# Current_SenseSchematic.net
KiCad netlist of a schematic drawn in Altium Designer
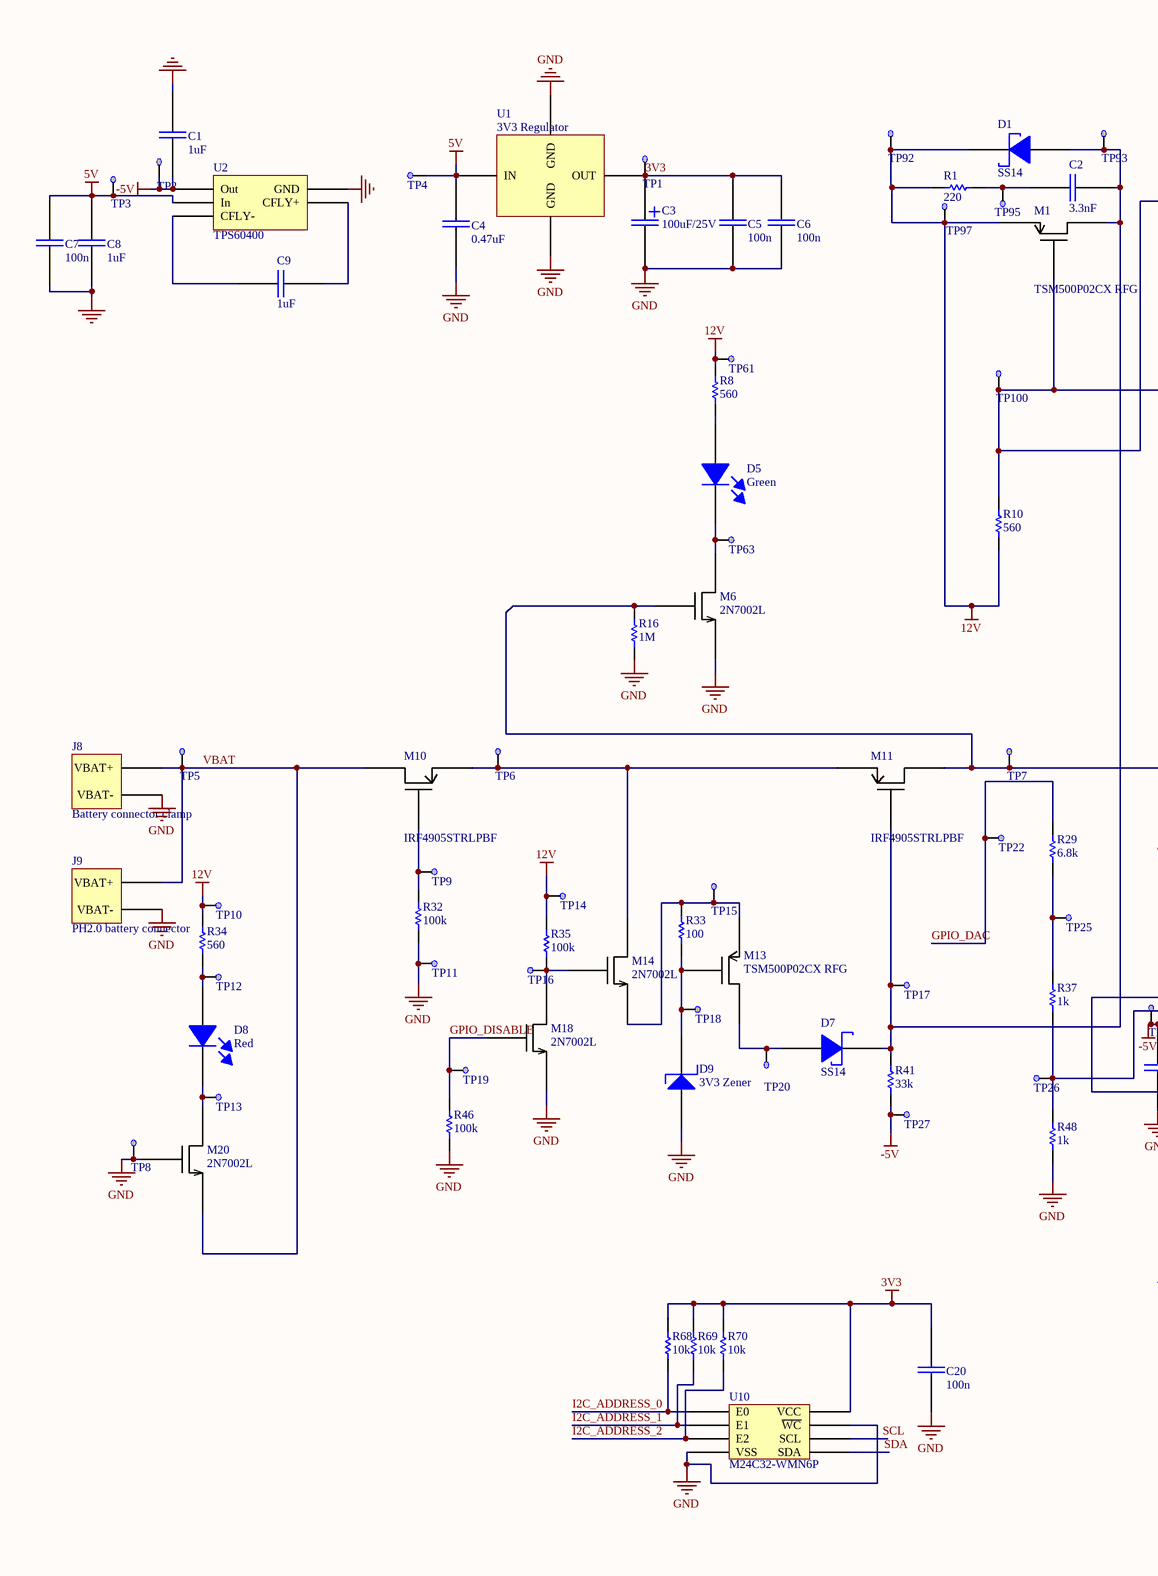
[diagram p0: Current_SenseSchematic.SchDoc, left]
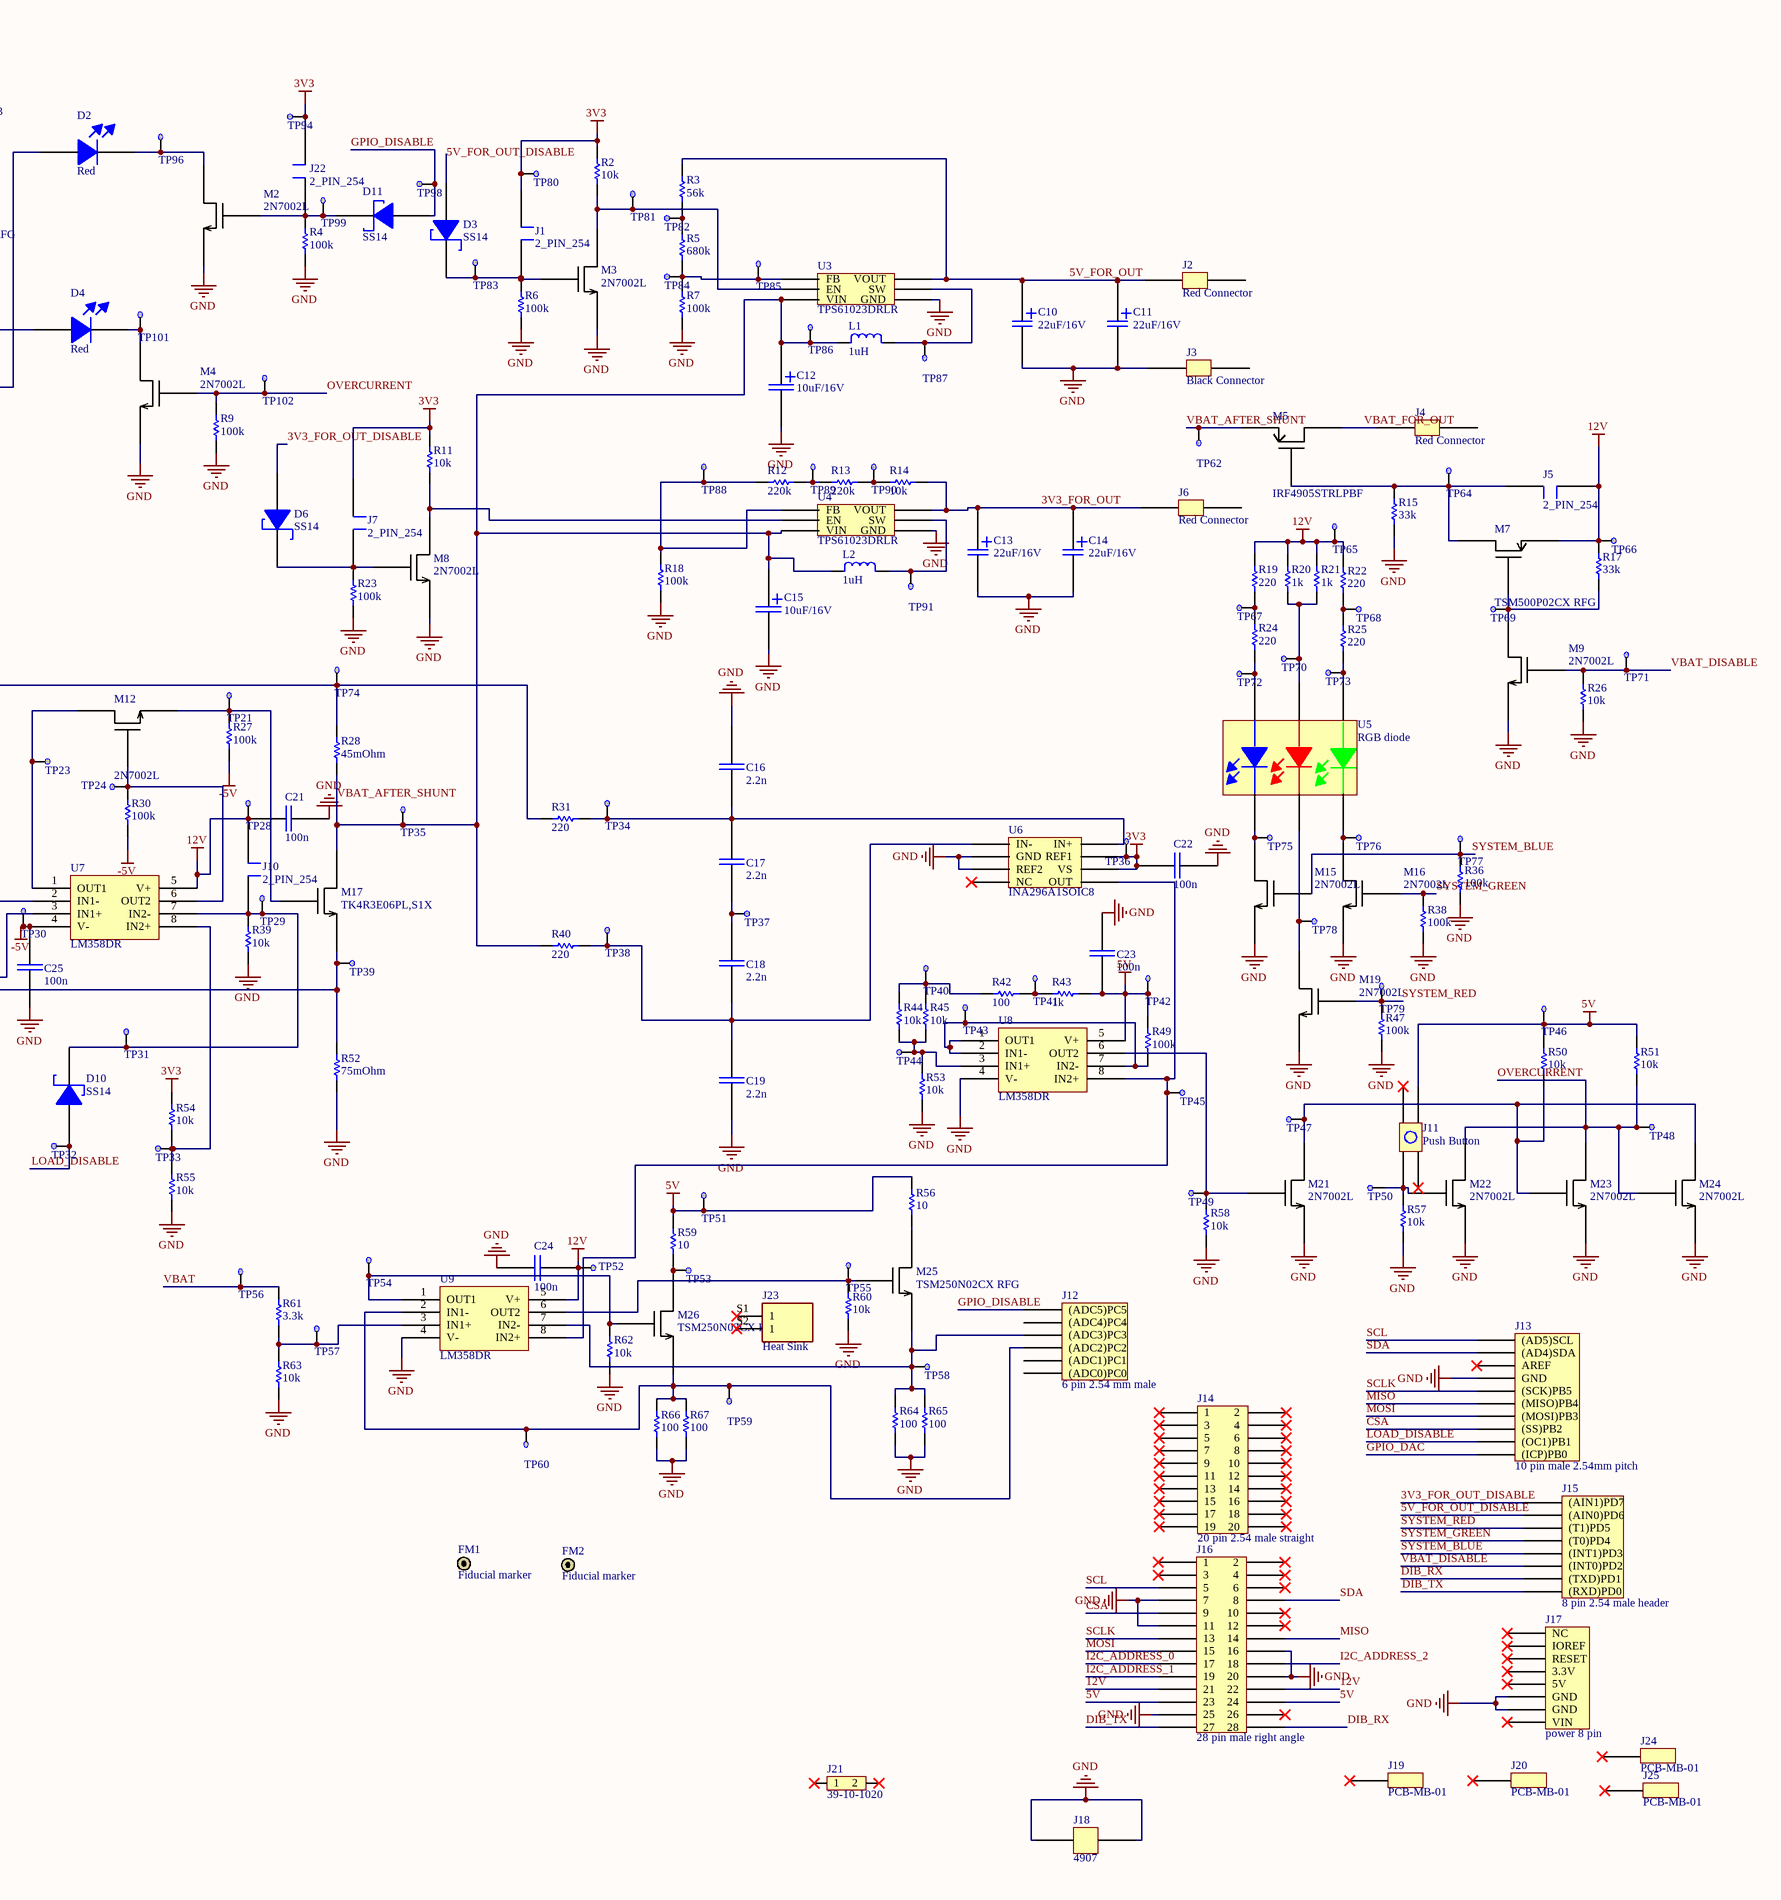
[diagram p1: Current_SenseSchematic.SchDoc, right]

(export (version "E")
  (design (tool "Eeschema 10.0.6"))
  (components
    (comp (ref "C1")
      (value "1uF")
      (footprint "1206Capacitor")
      (description "Multilayer Ceramic Capacitor, 1 uF, 50 V, ± 10%, X7R, 1206 [3216 Metric]")
      (fields
        (field (name "MANUFACTURER") "KEMET")
        (field (name "MANUFACTURER PART NUMBER") "C1206C105K5RACTU")
      )
      (libsource (lib "Current_SenseSchematic") (part "C1206C105K5RACTU"))
    )
    (comp (ref "C2")
      (value "3.3nF")
      (footprint "1206Capacitor")
      (description "Cap Ceramic 0.0033uF 100V C0G 1% SMD 1206 125°C Embossed T/R")
      (fields
        (field (name "MANUFACTURER") "Kyocera AVX")
        (field (name "MANUFACTURER PART NUMBER") "12061A332FAT2A")
      )
      (libsource (lib "Current_SenseSchematic") (part "12061A332FAT2A"))
    )
    (comp (ref "C3")
      (value "100uF/25V")
      (footprint "CAPAE7366X60N")
      (description "Cap, 100Uf, 25V, Alu Elec, Hybrid, Smd Rohs Compliant: Yes ¦Wurth Elektronik 875585344001")
      (fields
        (field (name "MANUFACTURER") "Wurth Electronics")
        (field (name "MANUFACTURER PART NUMBER") "875585344001")
      )
      (libsource (lib "Current_SenseSchematic") (part "875585344001"))
    )
    (comp (ref "C4")
      (value "0.47uF")
      (footprint "1206Capacitor")
      (description "Cap Ceramic 0.47uF 25V X7R 5% SMD 1206 125°C Embossed T/R")
      (fields
        (field (name "MANUFACTURER") "Kyocera AVX")
        (field (name "MANUFACTURER PART NUMBER") "12063C474JAT2A")
      )
      (libsource (lib "Current_SenseSchematic") (part "12063C474JAT2A"))
    )
    (comp (ref "C5")
      (value "100n")
      (footprint "1206Capacitor")
      (description "1206 Standard 100nF Ceramic Multilayer Cap; 50VDC; +150C; X8R Dielectric; +/-10% SMD")
      (fields
        (field (name "MANUFACTURER") "Kyocera AVX")
        (field (name "MANUFACTURER PART NUMBER") "12065F104K4T2A")
      )
      (libsource (lib "Current_SenseSchematic") (part "12065F104K4T2A"))
    )
    (comp (ref "C6")
      (value "100n")
      (footprint "1206Capacitor")
      (description "1206 Standard 100nF Ceramic Multilayer Cap; 50VDC; +150C; X8R Dielectric; +/-10% SMD")
      (fields
        (field (name "MANUFACTURER") "Kyocera AVX")
        (field (name "MANUFACTURER PART NUMBER") "12065F104K4T2A")
      )
      (libsource (lib "Current_SenseSchematic") (part "12065F104K4T2A"))
    )
    (comp (ref "C7")
      (value "100n")
      (footprint "1206Capacitor")
      (description "1206 Standard 100nF Ceramic Multilayer Cap; 50VDC; +150C; X8R Dielectric; +/-10% SMD")
      (fields
        (field (name "MANUFACTURER") "Kyocera AVX")
        (field (name "MANUFACTURER PART NUMBER") "12065F104K4T2A")
      )
      (libsource (lib "Current_SenseSchematic") (part "12065F104K4T2A"))
    )
    (comp (ref "C8")
      (value "1uF")
      (footprint "1206Capacitor")
      (description "Multilayer Ceramic Capacitor, 1 uF, 50 V, ± 10%, X7R, 1206 [3216 Metric]")
      (fields
        (field (name "MANUFACTURER") "KEMET")
        (field (name "MANUFACTURER PART NUMBER") "C1206C105K5RACTU")
      )
      (libsource (lib "Current_SenseSchematic") (part "C1206C105K5RACTU"))
    )
    (comp (ref "C9")
      (value "1uF")
      (footprint "1206Capacitor")
      (description "Multilayer Ceramic Capacitor, 1 uF, 50 V, ± 10%, X7R, 1206 [3216 Metric]")
      (fields
        (field (name "MANUFACTURER") "KEMET")
        (field (name "MANUFACTURER PART NUMBER") "C1206C105K5RACTU")
      )
      (libsource (lib "Current_SenseSchematic") (part "C1206C105K5RACTU"))
    )
    (comp (ref "C10")
      (value "22uF/16V")
      (footprint "22uF/16V")
      (description "Aluminum Electrolytic Capacitors - SMD 22uF 16V")
      (fields
        (field (name "MANUFACTURER") "United Chemi-Con")
        (field (name "MANUFACTURER PART NUMBER") "MVJ16VC22RME60TP")
      )
      (libsource (lib "Current_SenseSchematic") (part "MVJ16VC22RME60TP"))
    )
    (comp (ref "C11")
      (value "22uF/16V")
      (footprint "22uF/16V")
      (description "Aluminum Electrolytic Capacitors - SMD 22uF 16V")
      (fields
        (field (name "MANUFACTURER") "United Chemi-Con")
        (field (name "MANUFACTURER PART NUMBER") "MVJ16VC22RME60TP")
      )
      (libsource (lib "Current_SenseSchematic") (part "MVJ16VC22RME60TP"))
    )
    (comp (ref "C12")
      (value "10uF/16V")
      (footprint "10uF/16V Electrolytic")
      (description "Aluminum Electrolytic Capacitor, 10 uF, 16 V, ± 20%, 1000 hours @ 105°C, Radial Can - SMD")
      (fields
        (field (name "MANUFACTURER") "Panasonic")
        (field (name "MANUFACTURER PART NUMBER") "EEE-HA1C100R")
      )
      (libsource (lib "Current_SenseSchematic") (part "EEE-HA1C100R"))
    )
    (comp (ref "C13")
      (value "22uF/16V")
      (footprint "22uF/16V")
      (description "Aluminum Electrolytic Capacitors - SMD 22uF 16V")
      (fields
        (field (name "MANUFACTURER") "United Chemi-Con")
        (field (name "MANUFACTURER PART NUMBER") "MVJ16VC22RME60TP")
      )
      (libsource (lib "Current_SenseSchematic") (part "MVJ16VC22RME60TP"))
    )
    (comp (ref "C14")
      (value "22uF/16V")
      (footprint "22uF/16V")
      (description "Aluminum Electrolytic Capacitors - SMD 22uF 16V")
      (fields
        (field (name "MANUFACTURER") "United Chemi-Con")
        (field (name "MANUFACTURER PART NUMBER") "MVJ16VC22RME60TP")
      )
      (libsource (lib "Current_SenseSchematic") (part "MVJ16VC22RME60TP"))
    )
    (comp (ref "C15")
      (value "10uF/16V")
      (footprint "10uF/16V Electrolytic")
      (description "Aluminum Electrolytic Capacitor, 10 uF, 16 V, ± 20%, 1000 hours @ 105°C, Radial Can - SMD")
      (fields
        (field (name "MANUFACTURER") "Panasonic")
        (field (name "MANUFACTURER PART NUMBER") "EEE-HA1C100R")
      )
      (libsource (lib "Current_SenseSchematic") (part "EEE-HA1C100R"))
    )
    (comp (ref "C16")
      (value "2.2n")
      (footprint "1206Capacitor")
      (description "1206 2.2 nF 50V ±10 % Tolerance X7R Surface Mount Multilayer Ceramic Capacitor")
      (fields
        (field (name "MANUFACTURER") "Kyocera AVX")
        (field (name "MANUFACTURER PART NUMBER") "12065C222KAZ2A")
      )
      (libsource (lib "Current_SenseSchematic") (part "12065C222KAZ2A"))
    )
    (comp (ref "C17")
      (value "2.2n")
      (footprint "1206Capacitor")
      (description "1206 2.2 nF 50V ±10 % Tolerance X7R Surface Mount Multilayer Ceramic Capacitor")
      (fields
        (field (name "MANUFACTURER") "Kyocera AVX")
        (field (name "MANUFACTURER PART NUMBER") "12065C222KAZ2A")
      )
      (libsource (lib "Current_SenseSchematic") (part "12065C222KAZ2A"))
    )
    (comp (ref "C18")
      (value "2.2n")
      (footprint "1206Capacitor")
      (description "1206 2.2 nF 50V ±10 % Tolerance X7R Surface Mount Multilayer Ceramic Capacitor")
      (fields
        (field (name "MANUFACTURER") "Kyocera AVX")
        (field (name "MANUFACTURER PART NUMBER") "12065C222KAZ2A")
      )
      (libsource (lib "Current_SenseSchematic") (part "12065C222KAZ2A"))
    )
    (comp (ref "C19")
      (value "2.2n")
      (footprint "1206Capacitor")
      (description "1206 2.2 nF 50V ±10 % Tolerance X7R Surface Mount Multilayer Ceramic Capacitor")
      (fields
        (field (name "MANUFACTURER") "Kyocera AVX")
        (field (name "MANUFACTURER PART NUMBER") "12065C222KAZ2A")
      )
      (libsource (lib "Current_SenseSchematic") (part "12065C222KAZ2A"))
    )
    (comp (ref "C20")
      (value "100n")
      (footprint "1206Capacitor")
      (description "1206 Standard 100nF Ceramic Multilayer Cap; 50VDC; +150C; X8R Dielectric; +/-10% SMD")
      (fields
        (field (name "MANUFACTURER") "Kyocera AVX")
        (field (name "MANUFACTURER PART NUMBER") "12065F104K4T2A")
      )
      (libsource (lib "Current_SenseSchematic") (part "12065F104K4T2A"))
    )
    (comp (ref "C21")
      (value "100n")
      (footprint "1206Capacitor")
      (description "1206 Standard 100nF Ceramic Multilayer Cap; 50VDC; +150C; X8R Dielectric; +/-10% SMD")
      (fields
        (field (name "MANUFACTURER") "Kyocera AVX")
        (field (name "MANUFACTURER PART NUMBER") "12065F104K4T2A")
      )
      (libsource (lib "Current_SenseSchematic") (part "12065F104K4T2A"))
    )
    (comp (ref "C22")
      (value "100n")
      (footprint "1206Capacitor")
      (description "1206 Standard 100nF Ceramic Multilayer Cap; 50VDC; +150C; X8R Dielectric; +/-10% SMD")
      (fields
        (field (name "MANUFACTURER") "Kyocera AVX")
        (field (name "MANUFACTURER PART NUMBER") "12065F104K4T2A")
      )
      (libsource (lib "Current_SenseSchematic") (part "12065F104K4T2A"))
    )
    (comp (ref "C23")
      (value "100n")
      (footprint "1206Capacitor")
      (description "1206 Standard 100nF Ceramic Multilayer Cap; 50VDC; +150C; X8R Dielectric; +/-10% SMD")
      (fields
        (field (name "MANUFACTURER") "Kyocera AVX")
        (field (name "MANUFACTURER PART NUMBER") "12065F104K4T2A")
      )
      (libsource (lib "Current_SenseSchematic") (part "12065F104K4T2A"))
    )
    (comp (ref "C24")
      (value "100n")
      (footprint "1206Capacitor")
      (description "1206 Standard 100nF Ceramic Multilayer Cap; 50VDC; +150C; X8R Dielectric; +/-10% SMD")
      (fields
        (field (name "MANUFACTURER") "Kyocera AVX")
        (field (name "MANUFACTURER PART NUMBER") "12065F104K4T2A")
      )
      (libsource (lib "Current_SenseSchematic") (part "12065F104K4T2A"))
    )
    (comp (ref "C25")
      (value "100n")
      (footprint "1206Capacitor")
      (description "1206 Standard 100nF Ceramic Multilayer Cap; 50VDC; +150C; X8R Dielectric; +/-10% SMD")
      (fields
        (field (name "MANUFACTURER") "Kyocera AVX")
        (field (name "MANUFACTURER PART NUMBER") "12065F104K4T2A")
      )
      (libsource (lib "Current_SenseSchematic") (part "12065F104K4T2A"))
    )
    (comp (ref "D1")
      (value "SS14")
      (footprint "DIOM5026X23N")
      (description "SS14 Series 500 mV 1 A 40 V Max Reverse Voltage Schottky Rectifier - DO-214AC")
      (fields (field (name "MANUFACTURER") "ON Semiconductor / Fairchild") (field (name "VOLTAGE") "40V"))
      (libsource (lib "Current_SenseSchematic") (part "SS14"))
    )
    (comp (ref "D2")
      (value "Red")
      (footprint "RED")
      (description "LED Red 20 mcd (Typ.) @ 25 C (Axial) 2.1 V (Typ.) @ 25 C (Forward) PCB")
      (fields
        (field (name "MANUFACTURER") "Lumex")
        (field (name "MANUFACTURER PART NUMBER") "SML-LXL1206GC-TR")
      )
      (libsource (lib "Current_SenseSchematic") (part "SML-LXL1206GC-TR"))
    )
    (comp (ref "D3")
      (value "SS14")
      (footprint "DIOM5026X23N")
      (description "SS14 Series 500 mV 1 A 40 V Max Reverse Voltage Schottky Rectifier - DO-214AC")
      (fields (field (name "MANUFACTURER") "ON Semiconductor / Fairchild") (field (name "VOLTAGE") "40V"))
      (libsource (lib "Current_SenseSchematic") (part "SS14"))
    )
    (comp (ref "D4")
      (value "Red")
      (footprint "RED")
      (description "LED Red 20 mcd (Typ.) @ 25 C (Axial) 2.1 V (Typ.) @ 25 C (Forward) PCB")
      (fields
        (field (name "MANUFACTURER") "Lumex")
        (field (name "MANUFACTURER PART NUMBER") "SML-LXL1206GC-TR")
      )
      (libsource (lib "Current_SenseSchematic") (part "SML-LXL1206GC-TR"))
    )
    (comp (ref "D5")
      (value "Green")
      (footprint "Green")
      (description "Led, Quasarbrite, Green, T-3/4 (1.8Mm), 574 Nm, 2.2 V, 20 Ma, 170 Mcd Rohs Compliant: Yes")
      (fields
        (field (name "MANUFACTURER") "Lumex")
        (field (name "MANUFACTURER PART NUMBER") "SML-LXL1209SUGC-TR")
      )
      (libsource (lib "Current_SenseSchematic") (part "SML-LXL1209SUGC-TR"))
    )
    (comp (ref "D6")
      (value "SS14")
      (footprint "DIOM5026X23N")
      (description "SS14 Series 500 mV 1 A 40 V Max Reverse Voltage Schottky Rectifier - DO-214AC")
      (fields (field (name "MANUFACTURER") "ON Semiconductor / Fairchild") (field (name "VOLTAGE") "40V"))
      (libsource (lib "Current_SenseSchematic") (part "SS14"))
    )
    (comp (ref "D7")
      (value "SS14")
      (footprint "DIOM5026X23N")
      (description "SS14 Series 500 mV 1 A 40 V Max Reverse Voltage Schottky Rectifier - DO-214AC")
      (fields (field (name "MANUFACTURER") "ON Semiconductor / Fairchild") (field (name "VOLTAGE") "40V"))
      (libsource (lib "Current_SenseSchematic") (part "SS14"))
    )
    (comp (ref "D8")
      (value "Red")
      (footprint "RED")
      (description "LED Red 20 mcd (Typ.) @ 25 C (Axial) 2.1 V (Typ.) @ 25 C (Forward) PCB")
      (fields
        (field (name "MANUFACTURER") "Lumex")
        (field (name "MANUFACTURER PART NUMBER") "SML-LXL1206GC-TR")
      )
      (libsource (lib "Current_SenseSchematic") (part "SML-LXL1206GC-TR"))
    )
    (comp (ref "D9")
      (value "3V3 Zener")
      (footprint "DIOMELF3515N")
      (description "MMELF, 500mW, 2%, Small Signal Zener Diode")
      (fields
        (field (name "MANUFACTURER") "Taiwan Semiconductor")
        (field (name "MANUFACTURER PART NUMBER") "BZT55B3V3 L1G")
      )
      (libsource (lib "Current_SenseSchematic") (part "BZT55B3V3 L1G"))
    )
    (comp (ref "D10")
      (value "SS14")
      (footprint "DIOM5026X23N")
      (description "SS14 Series 500 mV 1 A 40 V Max Reverse Voltage Schottky Rectifier - DO-214AC")
      (fields (field (name "MANUFACTURER") "ON Semiconductor / Fairchild") (field (name "VOLTAGE") "40V"))
      (libsource (lib "Current_SenseSchematic") (part "SS14"))
    )
    (comp (ref "D11")
      (value "SS14")
      (footprint "DIOM5026X23N")
      (description "SS14 Series 500 mV 1 A 40 V Max Reverse Voltage Schottky Rectifier - DO-214AC")
      (fields (field (name "MANUFACTURER") "ON Semiconductor / Fairchild") (field (name "VOLTAGE") "40V"))
      (libsource (lib "Current_SenseSchematic") (part "SS14"))
    )
    (comp (ref "FM1")
      (value "Fiducial marker")
      (footprint "Fiducal Marker")
      (libsource (lib "Current_SenseSchematic") (part "FM"))
    )
    (comp (ref "FM2")
      (value "Fiducial marker")
      (footprint "Fiducal Marker")
      (libsource (lib "Current_SenseSchematic") (part "FM"))
    )
    (comp (ref "J1")
      (value "2_PIN_254")
      (footprint "2_PIN_2.54mm")
      (description "Conn Unshrouded Header PL 2 POS 2.54mm Solder ST Thru-Hole")
      (fields (field (name "MANUFACTURER") "Omron") (field (name "MANUFACTURER PART NUMBER") "XG8T-0241"))
      (libsource (lib "Current_SenseSchematic") (part "XG8T-0241"))
    )
    (comp (ref "J2")
      (value "Red Connector")
      (footprint "RED CONNECTOR")
      (description "Connector, Pcb, 2CONTACTS")
      (fields (field (name "MANUFACTURER") "Deltron") (field (name "MANUFACTURER PART NUMBER") "571-0500"))
      (libsource (lib "Current_SenseSchematic") (part "571-0500"))
    )
    (comp (ref "J3")
      (value "Black Connector")
      (footprint "BLACK CONNECTOR")
      (description "Connector, Pcb, 2CONTACTS")
      (fields (field (name "MANUFACTURER") "Deltron") (field (name "MANUFACTURER PART NUMBER") "571-0100"))
      (libsource (lib "Current_SenseSchematic") (part "571-0100"))
    )
    (comp (ref "J4")
      (value "Red Connector")
      (footprint "RED CONNECTOR")
      (description "Connector, Pcb, 2CONTACTS")
      (fields (field (name "MANUFACTURER") "Deltron") (field (name "MANUFACTURER PART NUMBER") "571-0500"))
      (libsource (lib "Current_SenseSchematic") (part "571-0500"))
    )
    (comp (ref "J5")
      (value "2_PIN_254")
      (footprint "2_PIN_2.54mm")
      (description "Conn Unshrouded Header PL 2 POS 2.54mm Solder ST Thru-Hole")
      (fields (field (name "MANUFACTURER") "Omron") (field (name "MANUFACTURER PART NUMBER") "XG8T-0241"))
      (libsource (lib "Current_SenseSchematic") (part "XG8T-0241"))
    )
    (comp (ref "J6")
      (value "Red Connector")
      (footprint "RED CONNECTOR")
      (description "Connector, Pcb, 2CONTACTS")
      (fields (field (name "MANUFACTURER") "Deltron") (field (name "MANUFACTURER PART NUMBER") "571-0500"))
      (libsource (lib "Current_SenseSchematic") (part "571-0500"))
    )
    (comp (ref "J7")
      (value "2_PIN_254")
      (footprint "2_PIN_2.54mm")
      (description "Conn Unshrouded Header PL 2 POS 2.54mm Solder ST Thru-Hole")
      (fields (field (name "MANUFACTURER") "Omron") (field (name "MANUFACTURER PART NUMBER") "XG8T-0241"))
      (libsource (lib "Current_SenseSchematic") (part "XG8T-0241"))
    )
    (comp (ref "J8")
      (value "Battery connector clamp")
      (footprint "2.54mm CLAMP connector")
      (description "Conn PC Board Terminal Block Receptacle 2 POS 2.54mm RA Through Hole 10A")
      (fields
        (field (name "MANUFACTURER") "TE Connectivity")
        (field (name "MANUFACTURER PART NUMBER") "282834-2")
      )
      (libsource (lib "Current_SenseSchematic") (part "282834-2"))
    )
    (comp (ref "J9")
      (value "PH2.0 battery connector")
      (footprint "PH2.0 connector")
      (description "Connector, Header, 2Pos, 1Rows, 2Mm Rohs Compliant: Yes")
      (fields
        (field (name "MANUFACTURER") "TE Connectivity")
        (field (name "MANUFACTURER PART NUMBER") "292133-2")
      )
      (libsource (lib "Current_SenseSchematic") (part "292133-2"))
    )
    (comp (ref "J10")
      (value "2_PIN_254")
      (footprint "2_PIN_2.54mm")
      (description "Conn Unshrouded Header PL 2 POS 2.54mm Solder ST Thru-Hole")
      (fields (field (name "MANUFACTURER") "Omron") (field (name "MANUFACTURER PART NUMBER") "XG8T-0241"))
      (libsource (lib "Current_SenseSchematic") (part "XG8T-0241"))
    )
    (comp (ref "J11")
      (value "Push Button")
      (footprint "PUSH_BUTTON")
      (description "Switch Tactile N.O. SPST Round Button Gull Wing 0.05A 12VDC 1.57N SMD Tube")
      (fields
        (field (name "MANUFACTURER") "Diptronics")
        (field (name "MANUFACTURER PART NUMBER") "DTSM-61N-V-B")
      )
      (libsource (lib "Current_SenseSchematic") (part "DTSM-61N-V-B"))
    )
    (comp (ref "J12")
      (value "6 pin 2.54 mm male")
      (footprint "6_pin_header_male_2_54")
      (description "2.54mm (0.1\") Pitch SIL Vertical PC Tail Pin Header, 7mm mating pin height, tin, 6 contacts")
      (fields (field (name "MANUFACTURER") "Harwin") (field (name "MANUFACTURER PART NUMBER") "M20-9730646"))
      (libsource (lib "Current_SenseSchematic") (part "M20-9730646"))
    )
    (comp (ref "J13")
      (value "10 pin male 2.54mm pitch")
      (footprint "10_pin_header_male_2_54")
      (description "Conn Unshrouded Header HDR 50 POS 2.54mm Solder ST Thru-Hole Box")
      (fields
        (field (name "MANUFACTURER") "TE Connectivity")
        (field (name "MANUFACTURER PART NUMBER") "5-825433-0")
      )
      (libsource (lib "Current_SenseSchematic") (part "5-825433-0"))
    )
    (comp (ref "J14")
      (value "20 pin 2.54 male straight")
      (footprint "20_pin_header_angled_female_2_54_mm")
      (description "Conn, Header, 20POS, 2ROW, 2.54MM Rohs Compliant: Yes")
      (fields (field (name "MANUFACTURER") "Harwin") (field (name "MANUFACTURER PART NUMBER") "M20-9721045"))
      (libsource (lib "Current_SenseSchematic") (part "M20-9721045"))
    )
    (comp (ref "J15")
      (value "8 pin 2.54 male header")
      (footprint "8_pin_header_male_2_54")
      (description "2.54MM Pitch, Srsw, T/h, H")
      (fields (field (name "MANUFACTURER") "Molex") (field (name "MANUFACTURER PART NUMBER") "0878910808"))
      (libsource (lib "Current_SenseSchematic") (part "0878910808"))
    )
    (comp (ref "J16")
      (value "28 pin male right angle")
      (footprint "28_Pin_header_right_angle")
      (description "Headers & Wire Housings 28P 2R BRKAWAY HDR 2.54MM RA L-PRO SN")
      (fields (field (name "MANUFACTURER") "Molex") (field (name "MANUFACTURER PART NUMBER") "0717640028"))
      (libsource (lib "Current_SenseSchematic") (part "0717640028"))
    )
    (comp (ref "J17")
      (value "power 8 pin")
      (footprint "8_pin_header_male_2_54")
      (description "2.54MM Pitch, Srsw, T/h, H")
      (fields (field (name "MANUFACTURER") "Molex") (field (name "MANUFACTURER PART NUMBER") "0878910808"))
      (libsource (lib "Current_SenseSchematic") (part "0878910808_Power"))
    )
    (comp (ref "J18")
      (value "4907")
      (footprint "4907_footprint")
      (description "USB C SMT / THM Jack Connector - Power Only - Pack of 10")
      (fields (field (name "MANUFACTURER") "Keystone Electronics"))
      (libsource (lib "Current_SenseSchematic") (part "4907"))
    )
    (comp (ref "J19")
      (value "PCB-MB-01")
      (footprint "PCB-MB-01")
      (description "Installation BLock Colour: Transparent Material: Nylon 6/6 RMS-01")
      (fields (field (name "MANUFACTURER") "Essentra"))
      (libsource (lib "Current_SenseSchematic") (part "PCB-MB-01"))
    )
    (comp (ref "J20")
      (value "PCB-MB-01")
      (footprint "PCB-MB-01")
      (description "Installation BLock Colour: Transparent Material: Nylon 6/6 RMS-01")
      (fields (field (name "MANUFACTURER") "Essentra"))
      (libsource (lib "Current_SenseSchematic") (part "PCB-MB-01"))
    )
    (comp (ref "J21")
      (value "39-10-1020")
      (footprint "39-30-1020")
      (description "Connector Wire to Board Header 2 Position 4.2mm Solder Right Angle Thru-Hole Bag")
      (fields (field (name "MANUFACTURER") "Molex") (field (name "MANUFACTURER PART NUMBER") "0039301020+"))
      (libsource (lib "Current_SenseSchematic") (part "0039301020+"))
    )
    (comp (ref "J22")
      (value "2_PIN_254")
      (footprint "2_PIN_2.54mm")
      (description "Conn Unshrouded Header PL 2 POS 2.54mm Solder ST Thru-Hole")
      (fields (field (name "MANUFACTURER") "Omron") (field (name "MANUFACTURER PART NUMBER") "XG8T-0241"))
      (libsource (lib "Current_SenseSchematic") (part "XG8T-0241"))
    )
    (comp (ref "J23")
      (value "Heat Sink")
      (footprint "HEAT_SINK")
      (description "Heat Sink Passive TO-220 Radial Thru-Hole Aluminum 5.5°C/W Black Anodized")
      (fields
        (field (name "MANUFACTURER") "Aavid Thermalloy")
        (field (name "MANUFACTURER PART NUMBER") "529702B02500G")
      )
      (libsource (lib "Current_SenseSchematic") (part "529702B02500G"))
    )
    (comp (ref "J24")
      (value "PCB-MB-01")
      (footprint "PCB-MB-01")
      (description "Installation BLock Colour: Transparent Material: Nylon 6/6 RMS-01")
      (fields (field (name "MANUFACTURER") "Essentra"))
      (libsource (lib "Current_SenseSchematic") (part "PCB-MB-01"))
    )
    (comp (ref "J25")
      (value "PCB-MB-01")
      (footprint "PCB-MB-01")
      (description "Installation BLock Colour: Transparent Material: Nylon 6/6 RMS-01")
      (fields (field (name "MANUFACTURER") "Essentra"))
      (libsource (lib "Current_SenseSchematic") (part "PCB-MB-01"))
    )
    (comp (ref "L1")
      (value "1uH")
      (footprint "PA4333_7.4x6.8x3.2mm")
      (description "Drum Core Shielded Power Inductor Wirewound Ferrite 1uH 20% 1MHz 9.5A SMD T/R")
      (fields (field (name "MANUFACTURER") "Pulse") (field (name "MANUFACTURER PART NUMBER") "PA4333.102NLT"))
      (libsource (lib "Current_SenseSchematic") (part "PA4333.102NLT"))
    )
    (comp (ref "L2")
      (value "1uH")
      (footprint "PA4333_7.4x6.8x3.2mm")
      (description "Drum Core Shielded Power Inductor Wirewound Ferrite 1uH 20% 1MHz 9.5A SMD T/R")
      (fields (field (name "MANUFACTURER") "Pulse") (field (name "MANUFACTURER PART NUMBER") "PA4333.102NLT"))
      (libsource (lib "Current_SenseSchematic") (part "PA4333.102NLT"))
    )
    (comp (ref "M1")
      (value "TSM500P02CX RFG")
      (footprint "SOT95P240X100-3N")
      (description "Transistor Mosfet P-ch 20V 4.7A 3-PIN SOT-23 T/r")
      (fields (field (name "MANUFACTURER") "Taiwan Semiconductor"))
      (libsource (lib "Current_SenseSchematic") (part "TSM500P02CX RFG"))
    )
    (comp (ref "M2")
      (value "2N7002L")
      (footprint "SOT95P240X100-3N")
      (description "Mosfet, N-ch, Vdss 60VDC, Rds(on) 7.5 Ohms, ID+/-115MA, SOT-23 (TO-236), Pd 225MW, -55C")
      (fields (field (name "MANUFACTURER") "ON Semiconductor / Fairchild"))
      (libsource (lib "Current_SenseSchematic") (part "2N7002L"))
    )
    (comp (ref "M3")
      (value "2N7002L")
      (footprint "SOT95P240X100-3N")
      (description "Mosfet, N-ch, Vdss 60VDC, Rds(on) 7.5 Ohms, ID+/-115MA, SOT-23 (TO-236), Pd 225MW, -55C")
      (fields (field (name "MANUFACTURER") "ON Semiconductor / Fairchild"))
      (libsource (lib "Current_SenseSchematic") (part "2N7002L"))
    )
    (comp (ref "M4")
      (value "2N7002L")
      (footprint "SOT95P240X100-3N")
      (description "Mosfet, N-ch, Vdss 60VDC, Rds(on) 7.5 Ohms, ID+/-115MA, SOT-23 (TO-236), Pd 225MW, -55C")
      (fields (field (name "MANUFACTURER") "ON Semiconductor / Fairchild"))
      (libsource (lib "Current_SenseSchematic") (part "2N7002L"))
    )
    (comp (ref "M5")
      (value "IRF4905STRLPBF")
      (footprint "DPAK254P1524X483-3L")
      (description "Transistor: P-MOSFET; unipolar; -55V; -74A; 0.02ohm; 3.8W; -55+175 deg.C; SMD; TO263 (D2PAK)")
      (fields (field (name "MANUFACTURER") "Infineon"))
      (libsource (lib "Current_SenseSchematic") (part "IRF4905STRLPBF"))
    )
    (comp (ref "M6")
      (value "2N7002L")
      (footprint "SOT95P240X100-3N")
      (description "Mosfet, N-ch, Vdss 60VDC, Rds(on) 7.5 Ohms, ID+/-115MA, SOT-23 (TO-236), Pd 225MW, -55C")
      (fields (field (name "MANUFACTURER") "ON Semiconductor / Fairchild"))
      (libsource (lib "Current_SenseSchematic") (part "2N7002L"))
    )
    (comp (ref "M7")
      (value "TSM500P02CX RFG")
      (footprint "SOT95P240X100-3N")
      (description "Transistor Mosfet P-ch 20V 4.7A 3-PIN SOT-23 T/r")
      (fields (field (name "MANUFACTURER") "Taiwan Semiconductor"))
      (libsource (lib "Current_SenseSchematic") (part "TSM500P02CX RFG"))
    )
    (comp (ref "M8")
      (value "2N7002L")
      (footprint "SOT95P240X100-3N")
      (description "Mosfet, N-ch, Vdss 60VDC, Rds(on) 7.5 Ohms, ID+/-115MA, SOT-23 (TO-236), Pd 225MW, -55C")
      (fields (field (name "MANUFACTURER") "ON Semiconductor / Fairchild"))
      (libsource (lib "Current_SenseSchematic") (part "2N7002L"))
    )
    (comp (ref "M9")
      (value "2N7002L")
      (footprint "SOT95P240X100-3N")
      (description "Mosfet, N-ch, Vdss 60VDC, Rds(on) 7.5 Ohms, ID+/-115MA, SOT-23 (TO-236), Pd 225MW, -55C")
      (fields (field (name "MANUFACTURER") "ON Semiconductor / Fairchild"))
      (libsource (lib "Current_SenseSchematic") (part "2N7002L"))
    )
    (comp (ref "M10")
      (value "IRF4905STRLPBF")
      (footprint "DPAK254P1524X483-3L")
      (description "Transistor: P-MOSFET; unipolar; -55V; -74A; 0.02ohm; 3.8W; -55+175 deg.C; SMD; TO263 (D2PAK)")
      (fields (field (name "MANUFACTURER") "Infineon"))
      (libsource (lib "Current_SenseSchematic") (part "IRF4905STRLPBF"))
    )
    (comp (ref "M11")
      (value "IRF4905STRLPBF")
      (footprint "DPAK254P1524X483-3L")
      (description "Transistor: P-MOSFET; unipolar; -55V; -74A; 0.02ohm; 3.8W; -55+175 deg.C; SMD; TO263 (D2PAK)")
      (fields (field (name "MANUFACTURER") "Infineon"))
      (libsource (lib "Current_SenseSchematic") (part "IRF4905STRLPBF"))
    )
    (comp (ref "M12")
      (value "2N7002L")
      (footprint "SOT95P240X100-3N")
      (description "Mosfet, N-ch, Vdss 60VDC, Rds(on) 7.5 Ohms, ID+/-115MA, SOT-23 (TO-236), Pd 225MW, -55C")
      (fields (field (name "MANUFACTURER") "ON Semiconductor / Fairchild"))
      (libsource (lib "Current_SenseSchematic") (part "2N7002L"))
    )
    (comp (ref "M13")
      (value "TSM500P02CX RFG")
      (footprint "SOT95P240X100-3N")
      (description "Transistor Mosfet P-ch 20V 4.7A 3-PIN SOT-23 T/r")
      (fields (field (name "MANUFACTURER") "Taiwan Semiconductor"))
      (libsource (lib "Current_SenseSchematic") (part "TSM500P02CX RFG"))
    )
    (comp (ref "M14")
      (value "2N7002L")
      (footprint "SOT95P240X100-3N")
      (description "Mosfet, N-ch, Vdss 60VDC, Rds(on) 7.5 Ohms, ID+/-115MA, SOT-23 (TO-236), Pd 225MW, -55C")
      (fields (field (name "MANUFACTURER") "ON Semiconductor / Fairchild"))
      (libsource (lib "Current_SenseSchematic") (part "2N7002L"))
    )
    (comp (ref "M15")
      (value "2N7002L")
      (footprint "SOT95P240X100-3N")
      (description "Mosfet, N-ch, Vdss 60VDC, Rds(on) 7.5 Ohms, ID+/-115MA, SOT-23 (TO-236), Pd 225MW, -55C")
      (fields (field (name "MANUFACTURER") "ON Semiconductor / Fairchild"))
      (libsource (lib "Current_SenseSchematic") (part "2N7002L"))
    )
    (comp (ref "M16")
      (value "2N7002L")
      (footprint "SOT95P240X100-3N")
      (description "Mosfet, N-ch, Vdss 60VDC, Rds(on) 7.5 Ohms, ID+/-115MA, SOT-23 (TO-236), Pd 225MW, -55C")
      (fields (field (name "MANUFACTURER") "ON Semiconductor / Fairchild"))
      (libsource (lib "Current_SenseSchematic") (part "2N7002L"))
    )
    (comp (ref "M17")
      (value "TK4R3E06PL,S1X")
      (footprint "TO-220-3")
      (description "X35 Pb-F Power Mosfet Transistor To-220 Pd=87W F=1Mhz")
      (fields (field (name "MANUFACTURER") "Toshiba"))
      (libsource (lib "Current_SenseSchematic") (part "TK4R3E06PL,S1X"))
    )
    (comp (ref "M18")
      (value "2N7002L")
      (footprint "SOT95P240X100-3N")
      (description "Mosfet, N-ch, Vdss 60VDC, Rds(on) 7.5 Ohms, ID+/-115MA, SOT-23 (TO-236), Pd 225MW, -55C")
      (fields (field (name "MANUFACTURER") "ON Semiconductor / Fairchild"))
      (libsource (lib "Current_SenseSchematic") (part "2N7002L"))
    )
    (comp (ref "M19")
      (value "2N7002L")
      (footprint "SOT95P240X100-3N")
      (description "Mosfet, N-ch, Vdss 60VDC, Rds(on) 7.5 Ohms, ID+/-115MA, SOT-23 (TO-236), Pd 225MW, -55C")
      (fields (field (name "MANUFACTURER") "ON Semiconductor / Fairchild"))
      (libsource (lib "Current_SenseSchematic") (part "2N7002L"))
    )
    (comp (ref "M20")
      (value "2N7002L")
      (footprint "SOT95P240X100-3N")
      (description "Mosfet, N-ch, Vdss 60VDC, Rds(on) 7.5 Ohms, ID+/-115MA, SOT-23 (TO-236), Pd 225MW, -55C")
      (fields (field (name "MANUFACTURER") "ON Semiconductor / Fairchild"))
      (libsource (lib "Current_SenseSchematic") (part "2N7002L"))
    )
    (comp (ref "M21")
      (value "2N7002L")
      (footprint "SOT95P240X100-3N")
      (description "Mosfet, N-ch, Vdss 60VDC, Rds(on) 7.5 Ohms, ID+/-115MA, SOT-23 (TO-236), Pd 225MW, -55C")
      (fields (field (name "MANUFACTURER") "ON Semiconductor / Fairchild"))
      (libsource (lib "Current_SenseSchematic") (part "2N7002L"))
    )
    (comp (ref "M22")
      (value "2N7002L")
      (footprint "SOT95P240X100-3N")
      (description "Mosfet, N-ch, Vdss 60VDC, Rds(on) 7.5 Ohms, ID+/-115MA, SOT-23 (TO-236), Pd 225MW, -55C")
      (fields (field (name "MANUFACTURER") "ON Semiconductor / Fairchild"))
      (libsource (lib "Current_SenseSchematic") (part "2N7002L"))
    )
    (comp (ref "M23")
      (value "2N7002L")
      (footprint "SOT95P240X100-3N")
      (description "Mosfet, N-ch, Vdss 60VDC, Rds(on) 7.5 Ohms, ID+/-115MA, SOT-23 (TO-236), Pd 225MW, -55C")
      (fields (field (name "MANUFACTURER") "ON Semiconductor / Fairchild"))
      (libsource (lib "Current_SenseSchematic") (part "2N7002L"))
    )
    (comp (ref "M24")
      (value "2N7002L")
      (footprint "SOT95P240X100-3N")
      (description "Mosfet, N-ch, Vdss 60VDC, Rds(on) 7.5 Ohms, ID+/-115MA, SOT-23 (TO-236), Pd 225MW, -55C")
      (fields (field (name "MANUFACTURER") "ON Semiconductor / Fairchild"))
      (libsource (lib "Current_SenseSchematic") (part "2N7002L"))
    )
    (comp (ref "M25")
      (value "TSM250N02CX RFG")
      (footprint "SOT95P240X100-3N")
      (description "Transistor Power MOSFET N-CH 20V 5.8A 3-Pin SOT-23 T/R")
      (fields (field (name "MANUFACTURER") "Taiwan Semiconductor"))
      (libsource (lib "Current_SenseSchematic") (part "TSM250N02CX RFG"))
    )
    (comp (ref "M26")
      (value "TSM250N02CX RFG")
      (footprint "SOT95P240X100-3N")
      (description "Transistor Power MOSFET N-CH 20V 5.8A 3-Pin SOT-23 T/R")
      (fields (field (name "MANUFACTURER") "Taiwan Semiconductor"))
      (libsource (lib "Current_SenseSchematic") (part "TSM250N02CX RFG"))
    )
    (comp (ref "R1")
      (value "220")
      (footprint "RESISTOR1206")
      (description "Res, Aec-Q200, 220R, 1%, 0.5W, 1206 Rohs Compliant: Yes ¦Vishay RCC1206220RFKEA")
      (fields
        (field (name "MANUFACTURER") "Vishay Dale")
        (field (name "MANUFACTURER PART NUMBER") "RCC1206220RFKEA")
      )
      (libsource (lib "Current_SenseSchematic") (part "RCC1206220RFKEA"))
    )
    (comp (ref "R2")
      (value "10k")
      (footprint "RESISTOR1206")
      (description "SMD Chip Resistor, 10 kOhm, ± 5%, 250 mW, 1206 [3216 Metric], Thick Film, General Purpose")
      (fields
        (field (name "MANUFACTURER") "Bourns")
        (field (name "MANUFACTURER PART NUMBER") "CR1206-JW-103ELF")
      )
      (libsource (lib "Current_SenseSchematic") (part "CR1206-JW-103ELF"))
    )
    (comp (ref "R3")
      (value "56k")
      (footprint "RESISTOR1206")
      (description "Res Thick Film 1206 56K Ohm 1% 1/4W ±100ppm/°C Molded SMD SMD Paper Tape on Plastic Reel")
      (fields
        (field (name "MANUFACTURER") "Bourns")
        (field (name "MANUFACTURER PART NUMBER") "CR1206-FX-5602ELF")
      )
      (libsource (lib "Current_SenseSchematic") (part "CR1206-FX-5602ELF"))
    )
    (comp (ref "R4")
      (value "100k")
      (footprint "RESISTOR1206")
      (description "Res Thick Film 1206 100kOhm 1/4W Molded Paper T/R")
      (fields
        (field (name "MANUFACTURER") "Vishay Dale")
        (field (name "MANUFACTURER PART NUMBER") "RCG1206100KJNEA")
      )
      (libsource (lib "Current_SenseSchematic") (part "RCG1206100KJNEA"))
    )
    (comp (ref "R5")
      (value "680k")
      (footprint "RESISTOR1206")
      (description "RES SMD 680K OHM 5% 1/4W 1206")
      (fields
        (field (name "MANUFACTURER") "Bourns")
        (field (name "MANUFACTURER PART NUMBER") "CR1206-JW-684ELF")
      )
      (libsource (lib "Current_SenseSchematic") (part "CR1206-JW-684ELF"))
    )
    (comp (ref "R6")
      (value "100k")
      (footprint "RESISTOR1206")
      (description "Res Thick Film 1206 100kOhm 1/4W Molded Paper T/R")
      (fields
        (field (name "MANUFACTURER") "Vishay Dale")
        (field (name "MANUFACTURER PART NUMBER") "RCG1206100KJNEA")
      )
      (libsource (lib "Current_SenseSchematic") (part "RCG1206100KJNEA"))
    )
    (comp (ref "R7")
      (value "100k")
      (footprint "RESISTOR1206")
      (description "Res Thick Film 1206 100kOhm 1/4W Molded Paper T/R")
      (fields
        (field (name "MANUFACTURER") "Vishay Dale")
        (field (name "MANUFACTURER PART NUMBER") "RCG1206100KJNEA")
      )
      (libsource (lib "Current_SenseSchematic") (part "RCG1206100KJNEA"))
    )
    (comp (ref "R8")
      (value "560")
      (footprint "RESISTOR1206")
      (description "Res Thkflm D25/1206 560R Ohm 1% 100 ET6 E3 SMD")
      (fields
        (field (name "MANUFACTURER") "Vishay Dale")
        (field (name "MANUFACTURER PART NUMBER") "CRCW1206560RFKEC")
      )
      (libsource (lib "Current_SenseSchematic") (part "CRCW1206560RFKEC"))
    )
    (comp (ref "R9")
      (value "100k")
      (footprint "RESISTOR1206")
      (description "Res Thick Film 1206 100kOhm 1/4W Molded Paper T/R")
      (fields
        (field (name "MANUFACTURER") "Vishay Dale")
        (field (name "MANUFACTURER PART NUMBER") "RCG1206100KJNEA")
      )
      (libsource (lib "Current_SenseSchematic") (part "RCG1206100KJNEA"))
    )
    (comp (ref "R10")
      (value "560")
      (footprint "RESISTOR1206")
      (description "Res Thkflm D25/1206 560R Ohm 1% 100 ET6 E3 SMD")
      (fields
        (field (name "MANUFACTURER") "Vishay Dale")
        (field (name "MANUFACTURER PART NUMBER") "CRCW1206560RFKEC")
      )
      (libsource (lib "Current_SenseSchematic") (part "CRCW1206560RFKEC"))
    )
    (comp (ref "R11")
      (value "10k")
      (footprint "RESISTOR1206")
      (description "SMD Chip Resistor, 10 kOhm, ± 5%, 250 mW, 1206 [3216 Metric], Thick Film, General Purpose")
      (fields
        (field (name "MANUFACTURER") "Bourns")
        (field (name "MANUFACTURER PART NUMBER") "CR1206-JW-103ELF")
      )
      (libsource (lib "Current_SenseSchematic") (part "CR1206-JW-103ELF"))
    )
    (comp (ref "R12")
      (value "220k")
      (footprint "RESISTOR1206")
      (description "Resistor Thick Film 220kOhm 5% 2-Pin 1206 T/R")
      (fields
        (field (name "MANUFACTURER") "Bourns")
        (field (name "MANUFACTURER PART NUMBER") "CHP1206AJW-224ELF")
      )
      (libsource (lib "Current_SenseSchematic") (part "CHP1206AJW-224ELF"))
    )
    (comp (ref "R13")
      (value "220k")
      (footprint "RESISTOR1206")
      (description "Resistor Thick Film 220kOhm 5% 2-Pin 1206 T/R")
      (fields
        (field (name "MANUFACTURER") "Bourns")
        (field (name "MANUFACTURER PART NUMBER") "CHP1206AJW-224ELF")
      )
      (libsource (lib "Current_SenseSchematic") (part "CHP1206AJW-224ELF"))
    )
    (comp (ref "R14")
      (value "10k")
      (footprint "RESISTOR1206")
      (description "SMD Chip Resistor, 10 kOhm, ± 5%, 250 mW, 1206 [3216 Metric], Thick Film, General Purpose")
      (fields
        (field (name "MANUFACTURER") "Bourns")
        (field (name "MANUFACTURER PART NUMBER") "CR1206-JW-103ELF")
      )
      (libsource (lib "Current_SenseSchematic") (part "CR1206-JW-103ELF"))
    )
    (comp (ref "R15")
      (value "33k")
      (footprint "RESISTOR1206")
      (description "SMD Chip Resistor, 33 kOhm, ± 5%, 250 mW, 1206 [3216 Metric], Thick Film, General Purpose")
      (fields
        (field (name "MANUFACTURER") "Yageo")
        (field (name "MANUFACTURER PART NUMBER") "RC1206JR-0733KL")
      )
      (libsource (lib "Current_SenseSchematic") (part "RC1206JR-0733KL"))
    )
    (comp (ref "R16")
      (value "1M")
      (footprint "RESISTOR1206")
      (description "SMD Chip Resistor, 1 MOhm, ± 5%, 250 mW, 1206 [3216 Metric], Thick Film, General Purpose")
      (fields
        (field (name "MANUFACTURER") "Bourns")
        (field (name "MANUFACTURER PART NUMBER") "CR1206-JW-105ELF")
      )
      (libsource (lib "Current_SenseSchematic") (part "CR1206-JW-105ELF"))
    )
    (comp (ref "R17")
      (value "33k")
      (footprint "RESISTOR1206")
      (description "SMD Chip Resistor, 33 kOhm, ± 5%, 250 mW, 1206 [3216 Metric], Thick Film, General Purpose")
      (fields
        (field (name "MANUFACTURER") "Yageo")
        (field (name "MANUFACTURER PART NUMBER") "RC1206JR-0733KL")
      )
      (libsource (lib "Current_SenseSchematic") (part "RC1206JR-0733KL"))
    )
    (comp (ref "R18")
      (value "100k")
      (footprint "RESISTOR1206")
      (description "Res Thick Film 1206 100kOhm 1/4W Molded Paper T/R")
      (fields
        (field (name "MANUFACTURER") "Vishay Dale")
        (field (name "MANUFACTURER PART NUMBER") "RCG1206100KJNEA")
      )
      (libsource (lib "Current_SenseSchematic") (part "RCG1206100KJNEA"))
    )
    (comp (ref "R19")
      (value "220")
      (footprint "RESISTOR1206")
      (description "Res, Aec-Q200, 220R, 1%, 0.5W, 1206 Rohs Compliant: Yes ¦Vishay RCC1206220RFKEA")
      (fields
        (field (name "MANUFACTURER") "Vishay Dale")
        (field (name "MANUFACTURER PART NUMBER") "RCC1206220RFKEA")
      )
      (libsource (lib "Current_SenseSchematic") (part "RCC1206220RFKEA"))
    )
    (comp (ref "R20")
      (value "1k")
      (footprint "RESISTOR1206")
      (description "Res Thick Film 1206 1kOhm 5% 1/4W ±200ppm/K Molded Paper Tape")
      (fields
        (field (name "MANUFACTURER") "Vishay Dale")
        (field (name "MANUFACTURER PART NUMBER") "RCA12061K00JNEA")
      )
      (libsource (lib "Current_SenseSchematic") (part "RCA12061K00JNEA"))
    )
    (comp (ref "R21")
      (value "1k")
      (footprint "RESISTOR1206")
      (description "Res Thick Film 1206 1kOhm 5% 1/4W ±200ppm/K Molded Paper Tape")
      (fields
        (field (name "MANUFACTURER") "Vishay Dale")
        (field (name "MANUFACTURER PART NUMBER") "RCA12061K00JNEA")
      )
      (libsource (lib "Current_SenseSchematic") (part "RCA12061K00JNEA"))
    )
    (comp (ref "R22")
      (value "220")
      (footprint "RESISTOR1206")
      (description "Res, Aec-Q200, 220R, 1%, 0.5W, 1206 Rohs Compliant: Yes ¦Vishay RCC1206220RFKEA")
      (fields
        (field (name "MANUFACTURER") "Vishay Dale")
        (field (name "MANUFACTURER PART NUMBER") "RCC1206220RFKEA")
      )
      (libsource (lib "Current_SenseSchematic") (part "RCC1206220RFKEA"))
    )
    (comp (ref "R23")
      (value "100k")
      (footprint "RESISTOR1206")
      (description "Res Thick Film 1206 100kOhm 1/4W Molded Paper T/R")
      (fields
        (field (name "MANUFACTURER") "Vishay Dale")
        (field (name "MANUFACTURER PART NUMBER") "RCG1206100KJNEA")
      )
      (libsource (lib "Current_SenseSchematic") (part "RCG1206100KJNEA"))
    )
    (comp (ref "R24")
      (value "220")
      (footprint "RESISTOR1206")
      (description "Res, Aec-Q200, 220R, 1%, 0.5W, 1206 Rohs Compliant: Yes ¦Vishay RCC1206220RFKEA")
      (fields
        (field (name "MANUFACTURER") "Vishay Dale")
        (field (name "MANUFACTURER PART NUMBER") "RCC1206220RFKEA")
      )
      (libsource (lib "Current_SenseSchematic") (part "RCC1206220RFKEA"))
    )
    (comp (ref "R25")
      (value "220")
      (footprint "RESISTOR1206")
      (description "Res, Aec-Q200, 220R, 1%, 0.5W, 1206 Rohs Compliant: Yes ¦Vishay RCC1206220RFKEA")
      (fields
        (field (name "MANUFACTURER") "Vishay Dale")
        (field (name "MANUFACTURER PART NUMBER") "RCC1206220RFKEA")
      )
      (libsource (lib "Current_SenseSchematic") (part "RCC1206220RFKEA"))
    )
    (comp (ref "R26")
      (value "10k")
      (footprint "RESISTOR1206")
      (description "SMD Chip Resistor, 10 kOhm, ± 5%, 250 mW, 1206 [3216 Metric], Thick Film, General Purpose")
      (fields
        (field (name "MANUFACTURER") "Bourns")
        (field (name "MANUFACTURER PART NUMBER") "CR1206-JW-103ELF")
      )
      (libsource (lib "Current_SenseSchematic") (part "CR1206-JW-103ELF"))
    )
    (comp (ref "R27")
      (value "100k")
      (footprint "RESISTOR1206")
      (description "Res Thick Film 1206 100kOhm 1/4W Molded Paper T/R")
      (fields
        (field (name "MANUFACTURER") "Vishay Dale")
        (field (name "MANUFACTURER PART NUMBER") "RCG1206100KJNEA")
      )
      (libsource (lib "Current_SenseSchematic") (part "RCG1206100KJNEA"))
    )
    (comp (ref "R28")
      (value "45mOhm")
      (footprint "RESISTOR1206")
      (description "CURRENT SENSE, RESISTOR, WSLP1206.0451%EAe3 ¦ Vishay Dale WSLP1206R0450FEA")
      (fields
        (field (name "MANUFACTURER") "Vishay")
        (field (name "MANUFACTURER PART NUMBER") "WSLP1206R0450FEA")
      )
      (libsource (lib "Current_SenseSchematic") (part "WSLP1206R0450FEA"))
    )
    (comp (ref "R29")
      (value "6.8k")
      (footprint "RESISTOR1206")
      (description "Res Thick Film 1206 6.8K Ohm 1% 1/4W ±100ppm/°C Molded SMD SMD Paper Tape on Plastic Reel")
      (fields
        (field (name "MANUFACTURER") "Bourns")
        (field (name "MANUFACTURER PART NUMBER") "CR1206-FX-6801ELF")
      )
      (libsource (lib "Current_SenseSchematic") (part "CR1206-FX-6801ELF"))
    )
    (comp (ref "R30")
      (value "100k")
      (footprint "RESISTOR1206")
      (description "Res Thick Film 1206 100kOhm 1/4W Molded Paper T/R")
      (fields
        (field (name "MANUFACTURER") "Vishay Dale")
        (field (name "MANUFACTURER PART NUMBER") "RCG1206100KJNEA")
      )
      (libsource (lib "Current_SenseSchematic") (part "RCG1206100KJNEA"))
    )
    (comp (ref "R31")
      (value "220")
      (footprint "RESISTOR1206")
      (description "Res, Aec-Q200, 220R, 1%, 0.5W, 1206 Rohs Compliant: Yes ¦Vishay RCC1206220RFKEA")
      (fields
        (field (name "MANUFACTURER") "Vishay Dale")
        (field (name "MANUFACTURER PART NUMBER") "RCC1206220RFKEA")
      )
      (libsource (lib "Current_SenseSchematic") (part "RCC1206220RFKEA"))
    )
    (comp (ref "R32")
      (value "100k")
      (footprint "RESISTOR1206")
      (description "Res Thick Film 1206 100kOhm 1/4W Molded Paper T/R")
      (fields
        (field (name "MANUFACTURER") "Vishay Dale")
        (field (name "MANUFACTURER PART NUMBER") "RCG1206100KJNEA")
      )
      (libsource (lib "Current_SenseSchematic") (part "RCG1206100KJNEA"))
    )
    (comp (ref "R33")
      (value "100")
      (footprint "RESISTOR1206")
      (description "SMD Chip Resistor, 100 Ohm, ± 5%, 250 mW, 1206 [3216 Metric], Thick Film, General Purpose")
      (fields
        (field (name "MANUFACTURER") "Bourns")
        (field (name "MANUFACTURER PART NUMBER") "CR1206-JW-101ELF")
      )
      (libsource (lib "Current_SenseSchematic") (part "CR1206-JW-101ELF"))
    )
    (comp (ref "R34")
      (value "560")
      (footprint "RESISTOR1206")
      (description "Res Thkflm D25/1206 560R Ohm 1% 100 ET6 E3 SMD")
      (fields
        (field (name "MANUFACTURER") "Vishay Dale")
        (field (name "MANUFACTURER PART NUMBER") "CRCW1206560RFKEC")
      )
      (libsource (lib "Current_SenseSchematic") (part "CRCW1206560RFKEC"))
    )
    (comp (ref "R35")
      (value "100k")
      (footprint "RESISTOR1206")
      (description "Res Thick Film 1206 100kOhm 1/4W Molded Paper T/R")
      (fields
        (field (name "MANUFACTURER") "Vishay Dale")
        (field (name "MANUFACTURER PART NUMBER") "RCG1206100KJNEA")
      )
      (libsource (lib "Current_SenseSchematic") (part "RCG1206100KJNEA"))
    )
    (comp (ref "R36")
      (value "100k")
      (footprint "RESISTOR1206")
      (description "Res Thick Film 1206 100kOhm 1/4W Molded Paper T/R")
      (fields
        (field (name "MANUFACTURER") "Vishay Dale")
        (field (name "MANUFACTURER PART NUMBER") "RCG1206100KJNEA")
      )
      (libsource (lib "Current_SenseSchematic") (part "RCG1206100KJNEA"))
    )
    (comp (ref "R37")
      (value "1k")
      (footprint "RESISTOR1206")
      (description "Res Thick Film 1206 1kOhm 5% 1/4W ±200ppm/K Molded Paper Tape")
      (fields
        (field (name "MANUFACTURER") "Vishay Dale")
        (field (name "MANUFACTURER PART NUMBER") "RCA12061K00JNEA")
      )
      (libsource (lib "Current_SenseSchematic") (part "RCA12061K00JNEA"))
    )
    (comp (ref "R38")
      (value "100k")
      (footprint "RESISTOR1206")
      (description "Res Thick Film 1206 100kOhm 1/4W Molded Paper T/R")
      (fields
        (field (name "MANUFACTURER") "Vishay Dale")
        (field (name "MANUFACTURER PART NUMBER") "RCG1206100KJNEA")
      )
      (libsource (lib "Current_SenseSchematic") (part "RCG1206100KJNEA"))
    )
    (comp (ref "R39")
      (value "10k")
      (footprint "RESISTOR1206")
      (description "SMD Chip Resistor, 10 kOhm, ± 5%, 250 mW, 1206 [3216 Metric], Thick Film, General Purpose")
      (fields
        (field (name "MANUFACTURER") "Bourns")
        (field (name "MANUFACTURER PART NUMBER") "CR1206-JW-103ELF")
      )
      (libsource (lib "Current_SenseSchematic") (part "CR1206-JW-103ELF"))
    )
    (comp (ref "R40")
      (value "220")
      (footprint "RESISTOR1206")
      (description "Res, Aec-Q200, 220R, 1%, 0.5W, 1206 Rohs Compliant: Yes ¦Vishay RCC1206220RFKEA")
      (fields
        (field (name "MANUFACTURER") "Vishay Dale")
        (field (name "MANUFACTURER PART NUMBER") "RCC1206220RFKEA")
      )
      (libsource (lib "Current_SenseSchematic") (part "RCC1206220RFKEA"))
    )
    (comp (ref "R41")
      (value "33k")
      (footprint "RESISTOR1206")
      (description "SMD Chip Resistor, 33 kOhm, ± 5%, 250 mW, 1206 [3216 Metric], Thick Film, General Purpose")
      (fields
        (field (name "MANUFACTURER") "Yageo")
        (field (name "MANUFACTURER PART NUMBER") "RC1206JR-0733KL")
      )
      (libsource (lib "Current_SenseSchematic") (part "RC1206JR-0733KL"))
    )
    (comp (ref "R42")
      (value "100")
      (footprint "RESISTOR1206")
      (description "SMD Chip Resistor, 100 Ohm, ± 5%, 250 mW, 1206 [3216 Metric], Thick Film, General Purpose")
      (fields
        (field (name "MANUFACTURER") "Bourns")
        (field (name "MANUFACTURER PART NUMBER") "CR1206-JW-101ELF")
      )
      (libsource (lib "Current_SenseSchematic") (part "CR1206-JW-101ELF"))
    )
    (comp (ref "R43")
      (value "1k")
      (footprint "RESISTOR1206")
      (description "Res Thick Film 1206 1kOhm 5% 1/4W ±200ppm/K Molded Paper Tape")
      (fields
        (field (name "MANUFACTURER") "Vishay Dale")
        (field (name "MANUFACTURER PART NUMBER") "RCA12061K00JNEA")
      )
      (libsource (lib "Current_SenseSchematic") (part "RCA12061K00JNEA"))
    )
    (comp (ref "R44")
      (value "10k")
      (footprint "RESISTOR1206")
      (description "SMD Chip Resistor, 10 kOhm, ± 5%, 250 mW, 1206 [3216 Metric], Thick Film, General Purpose")
      (fields
        (field (name "MANUFACTURER") "Bourns")
        (field (name "MANUFACTURER PART NUMBER") "CR1206-JW-103ELF")
      )
      (libsource (lib "Current_SenseSchematic") (part "CR1206-JW-103ELF"))
    )
    (comp (ref "R45")
      (value "10k")
      (footprint "RESISTOR1206")
      (description "SMD Chip Resistor, 10 kOhm, ± 5%, 250 mW, 1206 [3216 Metric], Thick Film, General Purpose")
      (fields
        (field (name "MANUFACTURER") "Bourns")
        (field (name "MANUFACTURER PART NUMBER") "CR1206-JW-103ELF")
      )
      (libsource (lib "Current_SenseSchematic") (part "CR1206-JW-103ELF"))
    )
    (comp (ref "R46")
      (value "100k")
      (footprint "RESISTOR1206")
      (description "Res Thick Film 1206 100kOhm 1/4W Molded Paper T/R")
      (fields
        (field (name "MANUFACTURER") "Vishay Dale")
        (field (name "MANUFACTURER PART NUMBER") "RCG1206100KJNEA")
      )
      (libsource (lib "Current_SenseSchematic") (part "RCG1206100KJNEA"))
    )
    (comp (ref "R47")
      (value "100k")
      (footprint "RESISTOR1206")
      (description "Res Thick Film 1206 100kOhm 1/4W Molded Paper T/R")
      (fields
        (field (name "MANUFACTURER") "Vishay Dale")
        (field (name "MANUFACTURER PART NUMBER") "RCG1206100KJNEA")
      )
      (libsource (lib "Current_SenseSchematic") (part "RCG1206100KJNEA"))
    )
    (comp (ref "R48")
      (value "1k")
      (footprint "RESISTOR1206")
      (description "Res Thick Film 1206 1kOhm 5% 1/4W ±200ppm/K Molded Paper Tape")
      (fields
        (field (name "MANUFACTURER") "Vishay Dale")
        (field (name "MANUFACTURER PART NUMBER") "RCA12061K00JNEA")
      )
      (libsource (lib "Current_SenseSchematic") (part "RCA12061K00JNEA"))
    )
    (comp (ref "R49")
      (value "100k")
      (footprint "RESISTOR1206")
      (description "Res Thick Film 1206 100kOhm 1/4W Molded Paper T/R")
      (fields
        (field (name "MANUFACTURER") "Vishay Dale")
        (field (name "MANUFACTURER PART NUMBER") "RCG1206100KJNEA")
      )
      (libsource (lib "Current_SenseSchematic") (part "RCG1206100KJNEA"))
    )
    (comp (ref "R50")
      (value "10k")
      (footprint "RESISTOR1206")
      (description "SMD Chip Resistor, 10 kOhm, ± 5%, 250 mW, 1206 [3216 Metric], Thick Film, General Purpose")
      (fields
        (field (name "MANUFACTURER") "Bourns")
        (field (name "MANUFACTURER PART NUMBER") "CR1206-JW-103ELF")
      )
      (libsource (lib "Current_SenseSchematic") (part "CR1206-JW-103ELF"))
    )
    (comp (ref "R51")
      (value "10k")
      (footprint "RESISTOR1206")
      (description "SMD Chip Resistor, 10 kOhm, ± 5%, 250 mW, 1206 [3216 Metric], Thick Film, General Purpose")
      (fields
        (field (name "MANUFACTURER") "Bourns")
        (field (name "MANUFACTURER PART NUMBER") "CR1206-JW-103ELF")
      )
      (libsource (lib "Current_SenseSchematic") (part "CR1206-JW-103ELF"))
    )
    (comp (ref "R52")
      (value "75mOhm")
      (footprint "RESISTOR2512")
      (description "Res Current Sense Metal Strip 2512 0.075 Ohm 1% 3W ±25ppm/°C Molded Emboss T/R")
      (fields
        (field (name "MANUFACTURER") "CGS")
        (field (name "MANUFACTURER PART NUMBER") "TLRP3A30CR075FTE")
      )
      (libsource (lib "Current_SenseSchematic") (part "TLRP3A30CR075FTE"))
    )
    (comp (ref "R53")
      (value "10k")
      (footprint "RESISTOR1206")
      (description "SMD Chip Resistor, 10 kOhm, ± 5%, 250 mW, 1206 [3216 Metric], Thick Film, General Purpose")
      (fields
        (field (name "MANUFACTURER") "Bourns")
        (field (name "MANUFACTURER PART NUMBER") "CR1206-JW-103ELF")
      )
      (libsource (lib "Current_SenseSchematic") (part "CR1206-JW-103ELF"))
    )
    (comp (ref "R54")
      (value "10k")
      (footprint "RESISTOR1206")
      (description "SMD Chip Resistor, 10 kOhm, ± 5%, 250 mW, 1206 [3216 Metric], Thick Film, General Purpose")
      (fields
        (field (name "MANUFACTURER") "Bourns")
        (field (name "MANUFACTURER PART NUMBER") "CR1206-JW-103ELF")
      )
      (libsource (lib "Current_SenseSchematic") (part "CR1206-JW-103ELF"))
    )
    (comp (ref "R55")
      (value "10k")
      (footprint "RESISTOR1206")
      (description "SMD Chip Resistor, 10 kOhm, ± 5%, 250 mW, 1206 [3216 Metric], Thick Film, General Purpose")
      (fields
        (field (name "MANUFACTURER") "Bourns")
        (field (name "MANUFACTURER PART NUMBER") "CR1206-JW-103ELF")
      )
      (libsource (lib "Current_SenseSchematic") (part "CR1206-JW-103ELF"))
    )
    (comp (ref "R56")
      (value "10")
      (footprint "RESISTOR1206")
      (description "Resistor, ResHighPowerA 1206 10R 1% 3/4W TC100")
      (fields
        (field (name "MANUFACTURER") "Bourns")
        (field (name "MANUFACTURER PART NUMBER") "CMP1206AFX-10R0ELF")
      )
      (libsource (lib "Current_SenseSchematic") (part "CMP1206AFX-10R0ELF"))
    )
    (comp (ref "R57")
      (value "10k")
      (footprint "RESISTOR1206")
      (description "SMD Chip Resistor, 10 kOhm, ± 5%, 250 mW, 1206 [3216 Metric], Thick Film, General Purpose")
      (fields
        (field (name "MANUFACTURER") "Bourns")
        (field (name "MANUFACTURER PART NUMBER") "CR1206-JW-103ELF")
      )
      (libsource (lib "Current_SenseSchematic") (part "CR1206-JW-103ELF"))
    )
    (comp (ref "R58")
      (value "10k")
      (footprint "RESISTOR1206")
      (description "SMD Chip Resistor, 10 kOhm, ± 5%, 250 mW, 1206 [3216 Metric], Thick Film, General Purpose")
      (fields
        (field (name "MANUFACTURER") "Bourns")
        (field (name "MANUFACTURER PART NUMBER") "CR1206-JW-103ELF")
      )
      (libsource (lib "Current_SenseSchematic") (part "CR1206-JW-103ELF"))
    )
    (comp (ref "R59")
      (value "10")
      (footprint "RESISTOR1206")
      (description "Resistor, ResHighPowerA 1206 10R 1% 3/4W TC100")
      (fields
        (field (name "MANUFACTURER") "Bourns")
        (field (name "MANUFACTURER PART NUMBER") "CMP1206AFX-10R0ELF")
      )
      (libsource (lib "Current_SenseSchematic") (part "CMP1206AFX-10R0ELF"))
    )
    (comp (ref "R60")
      (value "10k")
      (footprint "RESISTOR1206")
      (description "SMD Chip Resistor, 10 kOhm, ± 5%, 250 mW, 1206 [3216 Metric], Thick Film, General Purpose")
      (fields
        (field (name "MANUFACTURER") "Bourns")
        (field (name "MANUFACTURER PART NUMBER") "CR1206-JW-103ELF")
      )
      (libsource (lib "Current_SenseSchematic") (part "CR1206-JW-103ELF"))
    )
    (comp (ref "R61")
      (value "3.3k")
      (footprint "RESISTOR1206")
      (description "Res Thick Film 1206 3.3K Ohm 1% 1/4W ±100ppm/°C Molded SMD SMD Paper Tape on Plastic Reel")
      (fields
        (field (name "MANUFACTURER") "Bourns")
        (field (name "MANUFACTURER PART NUMBER") "CR1206-FX-3301ELF")
      )
      (libsource (lib "Current_SenseSchematic") (part "CR1206-FX-3301ELF"))
    )
    (comp (ref "R62")
      (value "10k")
      (footprint "RESISTOR1206")
      (description "SMD Chip Resistor, 10 kOhm, ± 5%, 250 mW, 1206 [3216 Metric], Thick Film, General Purpose")
      (fields
        (field (name "MANUFACTURER") "Bourns")
        (field (name "MANUFACTURER PART NUMBER") "CR1206-JW-103ELF")
      )
      (libsource (lib "Current_SenseSchematic") (part "CR1206-JW-103ELF"))
    )
    (comp (ref "R63")
      (value "10k")
      (footprint "RESISTOR1206")
      (description "SMD Chip Resistor, 10 kOhm, ± 5%, 250 mW, 1206 [3216 Metric], Thick Film, General Purpose")
      (fields
        (field (name "MANUFACTURER") "Bourns")
        (field (name "MANUFACTURER PART NUMBER") "CR1206-JW-103ELF")
      )
      (libsource (lib "Current_SenseSchematic") (part "CR1206-JW-103ELF"))
    )
    (comp (ref "R64")
      (value "100")
      (footprint "RESISTOR1206")
      (description "SMD Chip Resistor, 100 Ohm, ± 5%, 250 mW, 1206 [3216 Metric], Thick Film, General Purpose")
      (fields
        (field (name "MANUFACTURER") "Bourns")
        (field (name "MANUFACTURER PART NUMBER") "CR1206-JW-101ELF")
      )
      (libsource (lib "Current_SenseSchematic") (part "CR1206-JW-101ELF"))
    )
    (comp (ref "R65")
      (value "100")
      (footprint "RESISTOR1206")
      (description "SMD Chip Resistor, 100 Ohm, ± 5%, 250 mW, 1206 [3216 Metric], Thick Film, General Purpose")
      (fields
        (field (name "MANUFACTURER") "Bourns")
        (field (name "MANUFACTURER PART NUMBER") "CR1206-JW-101ELF")
      )
      (libsource (lib "Current_SenseSchematic") (part "CR1206-JW-101ELF"))
    )
    (comp (ref "R66")
      (value "100")
      (footprint "RESISTOR1206")
      (description "SMD Chip Resistor, 100 Ohm, ± 5%, 250 mW, 1206 [3216 Metric], Thick Film, General Purpose")
      (fields
        (field (name "MANUFACTURER") "Bourns")
        (field (name "MANUFACTURER PART NUMBER") "CR1206-JW-101ELF")
      )
      (libsource (lib "Current_SenseSchematic") (part "CR1206-JW-101ELF"))
    )
    (comp (ref "R67")
      (value "100")
      (footprint "RESISTOR1206")
      (description "SMD Chip Resistor, 100 Ohm, ± 5%, 250 mW, 1206 [3216 Metric], Thick Film, General Purpose")
      (fields
        (field (name "MANUFACTURER") "Bourns")
        (field (name "MANUFACTURER PART NUMBER") "CR1206-JW-101ELF")
      )
      (libsource (lib "Current_SenseSchematic") (part "CR1206-JW-101ELF"))
    )
    (comp (ref "R68")
      (value "10k")
      (footprint "RESISTOR1206")
      (description "SMD Chip Resistor, 10 kOhm, ± 5%, 250 mW, 1206 [3216 Metric], Thick Film, General Purpose")
      (fields
        (field (name "MANUFACTURER") "Bourns")
        (field (name "MANUFACTURER PART NUMBER") "CR1206-JW-103ELF")
      )
      (libsource (lib "Current_SenseSchematic") (part "CR1206-JW-103ELF"))
    )
    (comp (ref "R69")
      (value "10k")
      (footprint "RESISTOR1206")
      (description "SMD Chip Resistor, 10 kOhm, ± 5%, 250 mW, 1206 [3216 Metric], Thick Film, General Purpose")
      (fields
        (field (name "MANUFACTURER") "Bourns")
        (field (name "MANUFACTURER PART NUMBER") "CR1206-JW-103ELF")
      )
      (libsource (lib "Current_SenseSchematic") (part "CR1206-JW-103ELF"))
    )
    (comp (ref "R70")
      (value "10k")
      (footprint "RESISTOR1206")
      (description "SMD Chip Resistor, 10 kOhm, ± 5%, 250 mW, 1206 [3216 Metric], Thick Film, General Purpose")
      (fields
        (field (name "MANUFACTURER") "Bourns")
        (field (name "MANUFACTURER PART NUMBER") "CR1206-JW-103ELF")
      )
      (libsource (lib "Current_SenseSchematic") (part "CR1206-JW-103ELF"))
    )
    (comp (ref "TP1") (value "TestPoint") (footprint "TestPoint") (libsource (lib "") (part "TestPoint_1")))
    (comp (ref "TP2") (value "TestPoint") (footprint "TestPoint") (libsource (lib "") (part "TestPoint_1")))
    (comp (ref "TP3") (value "TestPoint") (footprint "TestPoint") (libsource (lib "") (part "TestPoint_1")))
    (comp (ref "TP4")
      (value "TestPoint")
      (footprint "TestPoint")
      (libsource (lib "Current_SenseSchematic") (part "TestPoint"))
    )
    (comp (ref "TP5") (value "TestPoint") (footprint "TestPoint") (libsource (lib "") (part "TestPoint_1")))
    (comp (ref "TP6") (value "TestPoint") (footprint "TestPoint") (libsource (lib "") (part "TestPoint_1")))
    (comp (ref "TP7") (value "TestPoint") (footprint "TestPoint") (libsource (lib "") (part "TestPoint_1")))
    (comp (ref "TP8") (value "TestPoint") (footprint "TestPoint") (libsource (lib "") (part "TestPoint_1")))
    (comp (ref "TP9") (value "TestPoint") (footprint "TestPoint") (libsource (lib "") (part "TestPoint_3")))
    (comp (ref "TP10") (value "TestPoint") (footprint "TestPoint") (libsource (lib "") (part "TestPoint_3")))
    (comp (ref "TP11") (value "TestPoint") (footprint "TestPoint") (libsource (lib "") (part "TestPoint_3")))
    (comp (ref "TP12") (value "TestPoint") (footprint "TestPoint") (libsource (lib "") (part "TestPoint_3")))
    (comp (ref "TP13") (value "TestPoint") (footprint "TestPoint") (libsource (lib "") (part "TestPoint_3")))
    (comp (ref "TP14") (value "TestPoint") (footprint "TestPoint") (libsource (lib "") (part "TestPoint_3")))
    (comp (ref "TP15") (value "TestPoint") (footprint "TestPoint") (libsource (lib "") (part "TestPoint_1")))
    (comp (ref "TP16")
      (value "TestPoint")
      (footprint "TestPoint")
      (libsource (lib "Current_SenseSchematic") (part "TestPoint"))
    )
    (comp (ref "TP17") (value "TestPoint") (footprint "TestPoint") (libsource (lib "") (part "TestPoint_3")))
    (comp (ref "TP18") (value "TestPoint") (footprint "TestPoint") (libsource (lib "") (part "TestPoint_3")))
    (comp (ref "TP19") (value "TestPoint") (footprint "TestPoint") (libsource (lib "") (part "TestPoint_3")))
    (comp (ref "TP20") (value "TestPoint") (footprint "TestPoint") (libsource (lib "") (part "TestPoint_2")))
    (comp (ref "TP21") (value "TestPoint") (footprint "TestPoint") (libsource (lib "") (part "TestPoint_1")))
    (comp (ref "TP22") (value "TestPoint") (footprint "TestPoint") (libsource (lib "") (part "TestPoint_3")))
    (comp (ref "TP23") (value "TestPoint") (footprint "TestPoint") (libsource (lib "") (part "TestPoint_3")))
    (comp (ref "TP24")
      (value "TestPoint")
      (footprint "TestPoint")
      (libsource (lib "Current_SenseSchematic") (part "TestPoint"))
    )
    (comp (ref "TP25") (value "TestPoint") (footprint "TestPoint") (libsource (lib "") (part "TestPoint_3")))
    (comp (ref "TP26")
      (value "TestPoint")
      (footprint "TestPoint")
      (libsource (lib "Current_SenseSchematic") (part "TestPoint"))
    )
    (comp (ref "TP27") (value "TestPoint") (footprint "TestPoint") (libsource (lib "") (part "TestPoint_3")))
    (comp (ref "TP28") (value "TestPoint") (footprint "TestPoint") (libsource (lib "") (part "TestPoint_1")))
    (comp (ref "TP29") (value "TestPoint") (footprint "TestPoint") (libsource (lib "") (part "TestPoint_1")))
    (comp (ref "TP30") (value "TestPoint") (footprint "TestPoint") (libsource (lib "") (part "TestPoint_1")))
    (comp (ref "TP31") (value "TestPoint") (footprint "TestPoint") (libsource (lib "") (part "TestPoint_1")))
    (comp (ref "TP32")
      (value "TestPoint")
      (footprint "TestPoint")
      (libsource (lib "Current_SenseSchematic") (part "TestPoint"))
    )
    (comp (ref "TP33")
      (value "TestPoint")
      (footprint "TestPoint")
      (libsource (lib "Current_SenseSchematic") (part "TestPoint"))
    )
    (comp (ref "TP34") (value "TestPoint") (footprint "TestPoint") (libsource (lib "") (part "TestPoint_1")))
    (comp (ref "TP35") (value "TestPoint") (footprint "TestPoint") (libsource (lib "") (part "TestPoint_1")))
    (comp (ref "TP36") (value "TestPoint") (footprint "TestPoint") (libsource (lib "") (part "TestPoint_1")))
    (comp (ref "TP37") (value "TestPoint") (footprint "TestPoint") (libsource (lib "") (part "TestPoint_3")))
    (comp (ref "TP38") (value "TestPoint") (footprint "TestPoint") (libsource (lib "") (part "TestPoint_1")))
    (comp (ref "TP39") (value "TestPoint") (footprint "TestPoint") (libsource (lib "") (part "TestPoint_3")))
    (comp (ref "TP40") (value "TestPoint") (footprint "TestPoint") (libsource (lib "") (part "TestPoint_1")))
    (comp (ref "TP41") (value "TestPoint") (footprint "TestPoint") (libsource (lib "") (part "TestPoint_1")))
    (comp (ref "TP42") (value "TestPoint") (footprint "TestPoint") (libsource (lib "") (part "TestPoint_1")))
    (comp (ref "TP43") (value "TestPoint") (footprint "TestPoint") (libsource (lib "") (part "TestPoint_1")))
    (comp (ref "TP44")
      (value "TestPoint")
      (footprint "TestPoint")
      (libsource (lib "Current_SenseSchematic") (part "TestPoint"))
    )
    (comp (ref "TP45") (value "TestPoint") (footprint "TestPoint") (libsource (lib "") (part "TestPoint_3")))
    (comp (ref "TP46") (value "TestPoint") (footprint "TestPoint") (libsource (lib "") (part "TestPoint_1")))
    (comp (ref "TP47")
      (value "TestPoint")
      (footprint "TestPoint")
      (libsource (lib "Current_SenseSchematic") (part "TestPoint"))
    )
    (comp (ref "TP48") (value "TestPoint") (footprint "TestPoint") (libsource (lib "") (part "TestPoint_3")))
    (comp (ref "TP49")
      (value "TestPoint")
      (footprint "TestPoint")
      (libsource (lib "Current_SenseSchematic") (part "TestPoint"))
    )
    (comp (ref "TP50")
      (value "TestPoint")
      (footprint "TestPoint")
      (libsource (lib "Current_SenseSchematic") (part "TestPoint"))
    )
    (comp (ref "TP51") (value "TestPoint") (footprint "TestPoint") (libsource (lib "") (part "TestPoint_1")))
    (comp (ref "TP52") (value "TestPoint") (footprint "TestPoint") (libsource (lib "") (part "TestPoint_3")))
    (comp (ref "TP53") (value "TestPoint") (footprint "TestPoint") (libsource (lib "") (part "TestPoint_3")))
    (comp (ref "TP54") (value "TestPoint") (footprint "TestPoint") (libsource (lib "") (part "TestPoint_1")))
    (comp (ref "TP55") (value "TestPoint") (footprint "TestPoint") (libsource (lib "") (part "TestPoint_1")))
    (comp (ref "TP56") (value "TestPoint") (footprint "TestPoint") (libsource (lib "") (part "TestPoint_1")))
    (comp (ref "TP57") (value "TestPoint") (footprint "TestPoint") (libsource (lib "") (part "TestPoint_1")))
    (comp (ref "TP58") (value "TestPoint") (footprint "TestPoint") (libsource (lib "") (part "TestPoint_3")))
    (comp (ref "TP59") (value "TestPoint") (footprint "TestPoint") (libsource (lib "") (part "TestPoint_2")))
    (comp (ref "TP60") (value "TestPoint") (footprint "TestPoint") (libsource (lib "") (part "TestPoint_2")))
    (comp (ref "TP61") (value "TestPoint") (footprint "TestPoint") (libsource (lib "") (part "TestPoint_3")))
    (comp (ref "TP62") (value "TestPoint") (footprint "TestPoint") (libsource (lib "") (part "TestPoint_2")))
    (comp (ref "TP63") (value "TestPoint") (footprint "TestPoint") (libsource (lib "") (part "TestPoint_3")))
    (comp (ref "TP64") (value "TestPoint") (footprint "TestPoint") (libsource (lib "") (part "TestPoint_1")))
    (comp (ref "TP65") (value "TestPoint") (footprint "TestPoint") (libsource (lib "") (part "TestPoint_1")))
    (comp (ref "TP66") (value "TestPoint") (footprint "TestPoint") (libsource (lib "") (part "TestPoint_3")))
    (comp (ref "TP67")
      (value "TestPoint")
      (footprint "TestPoint")
      (libsource (lib "Current_SenseSchematic") (part "TestPoint"))
    )
    (comp (ref "TP68") (value "TestPoint") (footprint "TestPoint") (libsource (lib "") (part "TestPoint_3")))
    (comp (ref "TP69")
      (value "TestPoint")
      (footprint "TestPoint")
      (libsource (lib "Current_SenseSchematic") (part "TestPoint"))
    )
    (comp (ref "TP70")
      (value "TestPoint")
      (footprint "TestPoint")
      (libsource (lib "Current_SenseSchematic") (part "TestPoint"))
    )
    (comp (ref "TP71") (value "TestPoint") (footprint "TestPoint") (libsource (lib "") (part "TestPoint_1")))
    (comp (ref "TP72")
      (value "TestPoint")
      (footprint "TestPoint")
      (libsource (lib "Current_SenseSchematic") (part "TestPoint"))
    )
    (comp (ref "TP73")
      (value "TestPoint")
      (footprint "TestPoint")
      (libsource (lib "Current_SenseSchematic") (part "TestPoint"))
    )
    (comp (ref "TP74") (value "TestPoint") (footprint "TestPoint") (libsource (lib "") (part "TestPoint_1")))
    (comp (ref "TP75") (value "TestPoint") (footprint "TestPoint") (libsource (lib "") (part "TestPoint_3")))
    (comp (ref "TP76") (value "TestPoint") (footprint "TestPoint") (libsource (lib "") (part "TestPoint_3")))
    (comp (ref "TP77") (value "TestPoint") (footprint "TestPoint") (libsource (lib "") (part "TestPoint_1")))
    (comp (ref "TP78") (value "TestPoint") (footprint "TestPoint") (libsource (lib "") (part "TestPoint_3")))
    (comp (ref "TP79") (value "TestPoint") (footprint "TestPoint") (libsource (lib "") (part "TestPoint_1")))
    (comp (ref "TP80") (value "TestPoint") (footprint "TestPoint") (libsource (lib "") (part "TestPoint_3")))
    (comp (ref "TP81") (value "TestPoint") (footprint "TestPoint") (libsource (lib "") (part "TestPoint_1")))
    (comp (ref "TP82")
      (value "TestPoint")
      (footprint "TestPoint")
      (libsource (lib "Current_SenseSchematic") (part "TestPoint"))
    )
    (comp (ref "TP83") (value "TestPoint") (footprint "TestPoint") (libsource (lib "") (part "TestPoint_1")))
    (comp (ref "TP84")
      (value "TestPoint")
      (footprint "TestPoint")
      (libsource (lib "Current_SenseSchematic") (part "TestPoint"))
    )
    (comp (ref "TP85") (value "TestPoint") (footprint "TestPoint") (libsource (lib "") (part "TestPoint_1")))
    (comp (ref "TP86") (value "TestPoint") (footprint "TestPoint") (libsource (lib "") (part "TestPoint_1")))
    (comp (ref "TP87") (value "TestPoint") (footprint "TestPoint") (libsource (lib "") (part "TestPoint_2")))
    (comp (ref "TP88") (value "TestPoint") (footprint "TestPoint") (libsource (lib "") (part "TestPoint_1")))
    (comp (ref "TP89") (value "TestPoint") (footprint "TestPoint") (libsource (lib "") (part "TestPoint_1")))
    (comp (ref "TP90") (value "TestPoint") (footprint "TestPoint") (libsource (lib "") (part "TestPoint_1")))
    (comp (ref "TP91") (value "TestPoint") (footprint "TestPoint") (libsource (lib "") (part "TestPoint_2")))
    (comp (ref "TP92") (value "TestPoint") (footprint "TestPoint") (libsource (lib "") (part "TestPoint_1")))
    (comp (ref "TP93") (value "TestPoint") (footprint "TestPoint") (libsource (lib "") (part "TestPoint_1")))
    (comp (ref "TP94")
      (value "TestPoint")
      (footprint "TestPoint")
      (libsource (lib "Current_SenseSchematic") (part "TestPoint"))
    )
    (comp (ref "TP95") (value "TestPoint") (footprint "TestPoint") (libsource (lib "") (part "TestPoint_2")))
    (comp (ref "TP96") (value "TestPoint") (footprint "TestPoint") (libsource (lib "") (part "TestPoint_1")))
    (comp (ref "TP97") (value "TestPoint") (footprint "TestPoint") (libsource (lib "") (part "TestPoint_1")))
    (comp (ref "TP98")
      (value "TestPoint")
      (footprint "TestPoint")
      (libsource (lib "Current_SenseSchematic") (part "TestPoint"))
    )
    (comp (ref "TP99") (value "TestPoint") (footprint "TestPoint") (libsource (lib "") (part "TestPoint_1")))
    (comp (ref "TP100") (value "TestPoint") (footprint "TestPoint") (libsource (lib "") (part "TestPoint_1")))
    (comp (ref "TP101") (value "TestPoint") (footprint "TestPoint") (libsource (lib "") (part "TestPoint_1")))
    (comp (ref "TP102") (value "TestPoint") (footprint "TestPoint") (libsource (lib "") (part "TestPoint_1")))
    (comp (ref "U1")
      (value "3V3 Regulator")
      (footprint "SOT230P700X180-4N")
      (description "IC REG LDO 3.3V 1A SOT223")
      (fields
        (field (name "MANUFACTURER") "TI National Semiconductor")
        (field (name "MANUFACTURER PART NUMBER") "LM3940IMP-3.3/NOPB")
      )
      (libsource (lib "Current_SenseSchematic") (part "LM3940IMP-3.3/NOPB"))
    )
    (comp (ref "U2")
      (value "TPS60400")
      (footprint "SOT95P280X135-5N")
      (description "60mA Charge Pump Voltage Inverter with Variable Switching Frequency 5-SOT-23 -40 to 85")
      (fields
        (field (name "MANUFACTURER") "Texas Instruments")
        (field (name "MANUFACTURER PART NUMBER") "TPS60400DBVT")
      )
      (libsource (lib "Current_SenseSchematic") (part "TPS60400DBVT"))
    )
    (comp (ref "U3")
      (value "TPS61023DRLR")
      (footprint "SOT563")
      (description "3.7-A boost converter with 0.5-V ultra-low input voltage 6-SOT-5X3 -40 to 125")
      (fields (field (name "MANUFACTURER") "Texas Instruments"))
      (libsource (lib "Current_SenseSchematic") (part "TPS61023DRLR"))
    )
    (comp (ref "U4")
      (value "TPS61023DRLR")
      (footprint "SOT563")
      (description "3.7-A boost converter with 0.5-V ultra-low input voltage 6-SOT-5X3 -40 to 125")
      (fields (field (name "MANUFACTURER") "Texas Instruments"))
      (libsource (lib "Current_SenseSchematic") (part "TPS61023DRLR"))
    )
    (comp (ref "U5")
      (value "RGB diode")
      (footprint "RGBDIODE")
      (description "WL-SFTW SMT full-color TOP LED waterclear")
      (fields
        (field (name "MANUFACTURER") "Wurth Electronics")
        (field (name "MANUFACTURER PART NUMBER") "150352M173300")
      )
      (libsource (lib "Current_SenseSchematic") (part "150352M173300"))
    )
    (comp (ref "U6")
      (value "INA296A1SOIC8")
      (footprint "SOIC127P600X175-8N")
      (description "Operational Amplifier, 1 Func, 150uV Offset-Max, PDSO5")
      (fields
        (field (name "MANUFACTURER") "Texas Instruments")
        (field (name "MANUFACTURER PART NUMBER") "INA296A1IDDFR")
      )
      (libsource (lib "Current_SenseSchematic") (part "INA296A1IDDFR"))
    )
    (comp (ref "U7")
      (value "LM358DR")
      (footprint "SOIC127P600X175-8N")
      (fields (field (name "MANUFACTURER") "Texas Instruments"))
      (libsource (lib "Current_SenseSchematic") (part "LM358DR"))
    )
    (comp (ref "U8")
      (value "LM358DR")
      (footprint "SOIC127P600X175-8N")
      (fields (field (name "MANUFACTURER") "Texas Instruments"))
      (libsource (lib "Current_SenseSchematic") (part "LM358DR"))
    )
    (comp (ref "U9")
      (value "LM358DR")
      (footprint "SOIC127P600X175-8N")
      (fields (field (name "MANUFACTURER") "Texas Instruments"))
      (libsource (lib "Current_SenseSchematic") (part "LM358DR"))
    )
    (comp (ref "U10")
      (value "M24C32-WMN6P")
      (footprint "SOIC127P600X175-8N")
      (description "M24C32 Series 32 Kb (4 K x 8) 2.5 V SMT Serial I²C Bus EEPROM - SOIC-8")
      (fields (field (name "MANUFACTURER") "STMicroelectronics"))
      (libsource (lib "Current_SenseSchematic") (part "M24C32-WMN6P"))
    )
  )
  (nets
    (net (code "1") (name "-5V") (class "Default")
      (node (ref "C1") (pin "1") (pinfunction "1_1") (pintype "passive"))
      (node (ref "C25") (pin "2") (pinfunction "2_2") (pintype "passive"))
      (node (ref "R27") (pin "1") (pinfunction "1_1") (pintype "passive"))
      (node (ref "R30") (pin "1") (pinfunction "1_1") (pintype "passive"))
      (node (ref "R41") (pin "1") (pinfunction "1_1") (pintype "passive"))
      (node (ref "TP2") (pin "1") (pinfunction "Test_Point_1") (pintype "passive"))
      (node (ref "TP27") (pin "1") (pinfunction "Test_Point_1") (pintype "passive"))
      (node (ref "TP30") (pin "1") (pinfunction "Test_Point_1") (pintype "passive"))
      (node (ref "U2") (pin "1") (pinfunction "Out_1") (pintype "passive"))
      (node (ref "U7") (pin "4") (pinfunction "V-_4") (pintype "passive"))
    )
    (net (code "2") (name "/3V3_FOR_OUT") (class "Default")
      (node (ref "C13") (pin "1") (pinfunction "C-_1") (pintype "passive"))
      (node (ref "C14") (pin "1") (pinfunction "C-_1") (pintype "passive"))
      (node (ref "J6") (pin "2") (pinfunction "2_2") (pintype "passive"))
      (node (ref "R14") (pin "2") (pinfunction "2_2") (pintype "passive"))
      (node (ref "U4") (pin "6") (pinfunction "VOUT_6") (pintype "passive"))
    )
    (net (code "3") (name "/3V3_FOR_OUT_DISABLE") (class "Default")
      (node (ref "D6") (pin "1") (pinfunction "A_1") (pintype "passive"))
      (node (ref "J15") (pin "8") (pinfunction "(AIN1)PD7_8") (pintype "passive"))
    )
    (net (code "4") (name "/5V_FOR_OUT") (class "Default")
      (node (ref "C10") (pin "1") (pinfunction "C-_1") (pintype "passive"))
      (node (ref "C11") (pin "1") (pinfunction "C-_1") (pintype "passive"))
      (node (ref "J2") (pin "2") (pinfunction "2_2") (pintype "passive"))
      (node (ref "R3") (pin "2") (pinfunction "2_2") (pintype "passive"))
      (node (ref "U3") (pin "6") (pinfunction "VOUT_6") (pintype "passive"))
    )
    (net (code "5") (name "/5V_FOR_OUT_DISABLE") (class "Default")
      (node (ref "D3") (pin "1") (pinfunction "A_1") (pintype "passive"))
      (node (ref "J15") (pin "7") (pinfunction "(AIN0)PD6_7") (pintype "passive"))
    )
    (net (code "6") (name "/CSA") (class "Default")
      (node (ref "J13") (pin "8") (pinfunction "(SS)PB2_8") (pintype "passive"))
      (node (ref "J16") (pin "9") (pinfunction "9_9") (pintype "passive"))
    )
    (net (code "7") (name "/DIB_RX") (class "Default")
      (node (ref "J15") (pin "2") (pinfunction "(TXD)PD1_2") (pintype "passive"))
      (node (ref "J16") (pin "28") (pinfunction "28_28") (pintype "passive"))
    )
    (net (code "8") (name "/DIB_TX") (class "Default")
      (node (ref "J15") (pin "1") (pinfunction "(RXD)PD0_1") (pintype "passive"))
      (node (ref "J16") (pin "27") (pinfunction "27_27") (pintype "passive"))
    )
    (net (code "9") (name "/GPIO_DAC") (class "Default")
      (node (ref "J13") (pin "10") (pinfunction "(ICP)PB0_10") (pintype "passive"))
      (node (ref "R29") (pin "2") (pinfunction "2_2") (pintype "passive"))
      (node (ref "TP22") (pin "1") (pinfunction "Test_Point_1") (pintype "passive"))
    )
    (net (code "10") (name "/GPIO_DISABLE") (class "Default")
      (node (ref "D11") (pin "1") (pinfunction "A_1") (pintype "passive"))
      (node (ref "J12") (pin "6") (pinfunction "(ADC5)PC5_6") (pintype "passive"))
      (node (ref "M18") (pin "1") (pinfunction "G_1") (pintype "passive"))
      (node (ref "R46") (pin "2") (pinfunction "2_2") (pintype "passive"))
      (node (ref "TP19") (pin "1") (pinfunction "Test_Point_1") (pintype "passive"))
      (node (ref "TP98") (pin "1") (pinfunction "Test_Point_1") (pintype "passive"))
    )
    (net (code "11") (name "/I2C_ADDRESS_0") (class "Default")
      (node (ref "J16") (pin "17") (pinfunction "17_17") (pintype "passive"))
      (node (ref "R68") (pin "1") (pinfunction "1_1") (pintype "passive"))
      (node (ref "U10") (pin "1") (pinfunction "E0_1") (pintype "passive"))
    )
    (net (code "12") (name "/I2C_ADDRESS_1") (class "Default")
      (node (ref "J16") (pin "19") (pinfunction "19_19") (pintype "passive"))
      (node (ref "R69") (pin "1") (pinfunction "1_1") (pintype "passive"))
      (node (ref "U10") (pin "2") (pinfunction "E1_2") (pintype "passive"))
    )
    (net (code "13") (name "/I2C_ADDRESS_2") (class "Default")
      (node (ref "J16") (pin "18") (pinfunction "18_18") (pintype "passive"))
      (node (ref "R70") (pin "1") (pinfunction "1_1") (pintype "passive"))
      (node (ref "U10") (pin "3") (pinfunction "E2_3") (pintype "passive"))
    )
    (net (code "14") (name "/LOAD_DISABLE") (class "Default")
      (node (ref "D10") (pin "1") (pinfunction "A_1") (pintype "passive"))
      (node (ref "J13") (pin "9") (pinfunction "(OC1)PB1_9") (pintype "passive"))
      (node (ref "TP32") (pin "1") (pinfunction "Test_Point_1") (pintype "passive"))
    )
    (net (code "15") (name "/MISO") (class "Default")
      (node (ref "J13") (pin "6") (pinfunction "(MISO)PB4_6") (pintype "passive"))
      (node (ref "J16") (pin "14") (pinfunction "14_14") (pintype "passive"))
    )
    (net (code "16") (name "/MOSI") (class "Default")
      (node (ref "J13") (pin "7") (pinfunction "(MOSI)PB3_7") (pintype "passive"))
      (node (ref "J16") (pin "15") (pinfunction "15_15") (pintype "passive"))
    )
    (net (code "17") (name "/OVERCURRENT") (class "Default")
      (node (ref "M22") (pin "3") (pinfunction "D_3") (pintype "passive"))
      (node (ref "M23") (pin "3") (pinfunction "D_3") (pintype "passive"))
      (node (ref "M24") (pin "1") (pinfunction "G_1") (pintype "passive"))
      (node (ref "M4") (pin "1") (pinfunction "G_1") (pintype "passive"))
      (node (ref "R51") (pin "1") (pinfunction "1_1") (pintype "passive"))
      (node (ref "R9") (pin "2") (pinfunction "2_2") (pintype "passive"))
      (node (ref "TP102") (pin "1") (pinfunction "Test_Point_1") (pintype "passive"))
      (node (ref "TP48") (pin "1") (pinfunction "Test_Point_1") (pintype "passive"))
    )
    (net (code "18") (name "/SCL") (class "Default")
      (node (ref "J13") (pin "1") (pinfunction "(AD5)SCL_1") (pintype "passive"))
      (node (ref "J16") (pin "5") (pinfunction "5_5") (pintype "passive"))
      (node (ref "U10") (pin "6") (pinfunction "SCL_6") (pintype "passive"))
    )
    (net (code "19") (name "/SCLK") (class "Default")
      (node (ref "J13") (pin "5") (pinfunction "(SCK)PB5_5") (pintype "passive"))
      (node (ref "J16") (pin "13") (pinfunction "13_13") (pintype "passive"))
    )
    (net (code "20") (name "/SDA") (class "Default")
      (node (ref "J13") (pin "2") (pinfunction "(AD4)SDA_2") (pintype "passive"))
      (node (ref "J16") (pin "8") (pinfunction "8_8") (pintype "passive"))
      (node (ref "U10") (pin "5") (pinfunction "SDA_5") (pintype "passive"))
    )
    (net (code "21") (name "/SYSTEM_BLUE") (class "Default")
      (node (ref "J15") (pin "4") (pinfunction "(INT1)PD3_4") (pintype "passive"))
      (node (ref "M15") (pin "1") (pinfunction "G_1") (pintype "passive"))
      (node (ref "R36") (pin "2") (pinfunction "2_2") (pintype "passive"))
      (node (ref "TP77") (pin "1") (pinfunction "Test_Point_1") (pintype "passive"))
    )
    (net (code "22") (name "/SYSTEM_GREEN") (class "Default")
      (node (ref "J15") (pin "5") (pinfunction "(T0)PD4_5") (pintype "passive"))
      (node (ref "M16") (pin "1") (pinfunction "G_1") (pintype "passive"))
      (node (ref "R38") (pin "2") (pinfunction "2_2") (pintype "passive"))
    )
    (net (code "23") (name "/SYSTEM_RED") (class "Default")
      (node (ref "J15") (pin "6") (pinfunction "(T1)PD5_6") (pintype "passive"))
      (node (ref "M19") (pin "1") (pinfunction "G_1") (pintype "passive"))
      (node (ref "R47") (pin "2") (pinfunction "2_2") (pintype "passive"))
      (node (ref "TP79") (pin "1") (pinfunction "Test_Point_1") (pintype "passive"))
    )
    (net (code "24") (name "/VBAT") (class "Default")
      (node (ref "J8") (pin "1") (pinfunction "VBAT+_1") (pintype "passive"))
      (node (ref "J9") (pin "1") (pinfunction "VBAT+_1") (pintype "passive"))
      (node (ref "M10") (pin "4") (pinfunction "D_4") (pintype "passive"))
      (node (ref "M20") (pin "2") (pinfunction "S_2") (pintype "passive"))
      (node (ref "R61") (pin "2") (pinfunction "2_2") (pintype "passive"))
      (node (ref "TP5") (pin "1") (pinfunction "Test_Point_1") (pintype "passive"))
      (node (ref "TP56") (pin "1") (pinfunction "Test_Point_1") (pintype "passive"))
    )
    (net (code "25") (name "/VBAT_AFTER_SHUNT") (class "Default")
      (node (ref "C12") (pin "1") (pinfunction "C-_1") (pintype "passive"))
      (node (ref "C15") (pin "1") (pinfunction "C-_1") (pintype "passive"))
      (node (ref "L1") (pin "1") (pinfunction "1_1") (pintype "passive"))
      (node (ref "L2") (pin "1") (pinfunction "1_1") (pintype "passive"))
      (node (ref "M17") (pin "2") (pinfunction "D_2") (pintype "passive"))
      (node (ref "M5") (pin "3") (pinfunction "S_3") (pintype "passive"))
      (node (ref "R28") (pin "1") (pinfunction "1_1") (pintype "passive"))
      (node (ref "R40") (pin "1") (pinfunction "1_1") (pintype "passive"))
      (node (ref "TP35") (pin "1") (pinfunction "Test_Point_1") (pintype "passive"))
      (node (ref "TP62") (pin "1") (pinfunction "Test_Point_1") (pintype "passive"))
      (node (ref "TP86") (pin "1") (pinfunction "Test_Point_1") (pintype "passive"))
      (node (ref "U3") (pin "3") (pinfunction "VIN_3") (pintype "passive"))
      (node (ref "U4") (pin "3") (pinfunction "VIN_3") (pintype "passive"))
    )
    (net (code "26") (name "/VBAT_DISABLE") (class "Default")
      (node (ref "J15") (pin "3") (pinfunction "(INT0)PD2_3") (pintype "passive"))
      (node (ref "M9") (pin "1") (pinfunction "G_1") (pintype "passive"))
      (node (ref "R26") (pin "2") (pinfunction "2_2") (pintype "passive"))
      (node (ref "TP71") (pin "1") (pinfunction "Test_Point_1") (pintype "passive"))
    )
    (net (code "27") (name "/VBAT_FOR_OUT") (class "Default")
      (node (ref "J4") (pin "2") (pinfunction "2_2") (pintype "passive"))
      (node (ref "M5") (pin "4") (pinfunction "D_4") (pintype "passive"))
    )
    (net (code "28") (name "3V3") (class "Default")
      (node (ref "C20") (pin "2") (pinfunction "2_2") (pintype "passive"))
      (node (ref "C22") (pin "1") (pinfunction "1_1") (pintype "passive"))
      (node (ref "C3") (pin "1") (pinfunction "C-_1") (pintype "passive"))
      (node (ref "C5") (pin "2") (pinfunction "2_2") (pintype "passive"))
      (node (ref "C6") (pin "2") (pinfunction "2_2") (pintype "passive"))
      (node (ref "J1") (pin "1") (pinfunction "1_1") (pintype "passive"))
      (node (ref "J22") (pin "2") (pinfunction "2_2") (pintype "passive"))
      (node (ref "J7") (pin "1") (pinfunction "1_1") (pintype "passive"))
      (node (ref "R11") (pin "2") (pinfunction "2_2") (pintype "passive"))
      (node (ref "R2") (pin "2") (pinfunction "2_2") (pintype "passive"))
      (node (ref "R54") (pin "2") (pinfunction "2_2") (pintype "passive"))
      (node (ref "R68") (pin "2") (pinfunction "2_2") (pintype "passive"))
      (node (ref "R69") (pin "2") (pinfunction "2_2") (pintype "passive"))
      (node (ref "R70") (pin "2") (pinfunction "2_2") (pintype "passive"))
      (node (ref "TP1") (pin "1") (pinfunction "Test_Point_1") (pintype "passive"))
      (node (ref "TP36") (pin "1") (pinfunction "Test_Point_1") (pintype "passive"))
      (node (ref "TP80") (pin "1") (pinfunction "Test_Point_1") (pintype "passive"))
      (node (ref "TP94") (pin "1") (pinfunction "Test_Point_1") (pintype "passive"))
      (node (ref "U1") (pin "3") (pinfunction "OUT_3") (pintype "passive"))
      (node (ref "U10") (pin "8") (pinfunction "VCC_8") (pintype "passive"))
      (node (ref "U6") (pin "6") (pinfunction "VS_6") (pintype "passive"))
      (node (ref "U6") (pin "7") (pinfunction "REF1_7") (pintype "passive"))
    )
    (net (code "29") (name "5V") (class "Default")
      (node (ref "C23") (pin "1") (pinfunction "1_1") (pintype "passive"))
      (node (ref "C4") (pin "2") (pinfunction "2_2") (pintype "passive"))
      (node (ref "C7") (pin "2") (pinfunction "2_2") (pintype "passive"))
      (node (ref "C8") (pin "2") (pinfunction "2_2") (pintype "passive"))
      (node (ref "J11") (pin "4") (pinfunction "4_4") (pintype "passive"))
      (node (ref "J16") (pin "23") (pinfunction "23_23") (pintype "passive"))
      (node (ref "J16") (pin "24") (pinfunction "24_24") (pintype "passive"))
      (node (ref "R43") (pin "1") (pinfunction "1_1") (pintype "passive"))
      (node (ref "R49") (pin "2") (pinfunction "2_2") (pintype "passive"))
      (node (ref "R50") (pin "2") (pinfunction "2_2") (pintype "passive"))
      (node (ref "R51") (pin "2") (pinfunction "2_2") (pintype "passive"))
      (node (ref "R56") (pin "2") (pinfunction "2_2") (pintype "passive"))
      (node (ref "R59") (pin "2") (pinfunction "2_2") (pintype "passive"))
      (node (ref "TP3") (pin "1") (pinfunction "Test_Point_1") (pintype "passive"))
      (node (ref "TP4") (pin "1") (pinfunction "Test_Point_1") (pintype "passive"))
      (node (ref "TP42") (pin "1") (pinfunction "Test_Point_1") (pintype "passive"))
      (node (ref "TP46") (pin "1") (pinfunction "Test_Point_1") (pintype "passive"))
      (node (ref "TP51") (pin "1") (pinfunction "Test_Point_1") (pintype "passive"))
      (node (ref "U1") (pin "1") (pinfunction "IN_1") (pintype "passive"))
      (node (ref "U2") (pin "2") (pinfunction "In_2") (pintype "passive"))
      (node (ref "U8") (pin "5") (pinfunction "V+_5") (pintype "passive"))
    )
    (net (code "30") (name "12V") (class "Default")
      (node (ref "C21") (pin "2") (pinfunction "2_2") (pintype "passive"))
      (node (ref "C24") (pin "2") (pinfunction "2_2") (pintype "passive"))
      (node (ref "D1") (pin "2") (pinfunction "K_2") (pintype "passive"))
      (node (ref "J10") (pin "1") (pinfunction "1_1") (pintype "passive"))
      (node (ref "J16") (pin "21") (pinfunction "21_21") (pintype "passive"))
      (node (ref "J16") (pin "22") (pinfunction "22_22") (pintype "passive"))
      (node (ref "J5") (pin "1") (pinfunction "1_1") (pintype "passive"))
      (node (ref "M1") (pin "3") (pinfunction "S_3") (pintype "passive"))
      (node (ref "M7") (pin "3") (pinfunction "S_3") (pintype "passive"))
      (node (ref "R1") (pin "1") (pinfunction "1_1") (pintype "passive"))
      (node (ref "R10") (pin "1") (pinfunction "1_1") (pintype "passive"))
      (node (ref "R17") (pin "2") (pinfunction "2_2") (pintype "passive"))
      (node (ref "R19") (pin "2") (pinfunction "2_2") (pintype "passive"))
      (node (ref "R20") (pin "2") (pinfunction "2_2") (pintype "passive"))
      (node (ref "R21") (pin "2") (pinfunction "2_2") (pintype "passive"))
      (node (ref "R22") (pin "2") (pinfunction "2_2") (pintype "passive"))
      (node (ref "R34") (pin "2") (pinfunction "2_2") (pintype "passive"))
      (node (ref "R35") (pin "2") (pinfunction "2_2") (pintype "passive"))
      (node (ref "R8") (pin "2") (pinfunction "2_2") (pintype "passive"))
      (node (ref "TP10") (pin "1") (pinfunction "Test_Point_1") (pintype "passive"))
      (node (ref "TP14") (pin "1") (pinfunction "Test_Point_1") (pintype "passive"))
      (node (ref "TP28") (pin "1") (pinfunction "Test_Point_1") (pintype "passive"))
      (node (ref "TP52") (pin "1") (pinfunction "Test_Point_1") (pintype "passive"))
      (node (ref "TP61") (pin "1") (pinfunction "Test_Point_1") (pintype "passive"))
      (node (ref "TP65") (pin "1") (pinfunction "Test_Point_1") (pintype "passive"))
      (node (ref "TP66") (pin "1") (pinfunction "Test_Point_1") (pintype "passive"))
      (node (ref "TP92") (pin "1") (pinfunction "Test_Point_1") (pintype "passive"))
      (node (ref "TP97") (pin "1") (pinfunction "Test_Point_1") (pintype "passive"))
      (node (ref "U7") (pin "5") (pinfunction "V+_5") (pintype "passive"))
      (node (ref "U9") (pin "5") (pinfunction "V+_5") (pintype "passive"))
    )
    (net (code "31") (name "GND") (class "Default")
      (node (ref "C1") (pin "2") (pinfunction "2_2") (pintype "passive"))
      (node (ref "C10") (pin "2") (pinfunction "C+_2") (pintype "passive"))
      (node (ref "C11") (pin "2") (pinfunction "C+_2") (pintype "passive"))
      (node (ref "C12") (pin "2") (pinfunction "C+_2") (pintype "passive"))
      (node (ref "C13") (pin "2") (pinfunction "C+_2") (pintype "passive"))
      (node (ref "C14") (pin "2") (pinfunction "C+_2") (pintype "passive"))
      (node (ref "C15") (pin "2") (pinfunction "C+_2") (pintype "passive"))
      (node (ref "C16") (pin "2") (pinfunction "2_2") (pintype "passive"))
      (node (ref "C19") (pin "1") (pinfunction "1_1") (pintype "passive"))
      (node (ref "C20") (pin "1") (pinfunction "1_1") (pintype "passive"))
      (node (ref "C21") (pin "1") (pinfunction "1_1") (pintype "passive"))
      (node (ref "C22") (pin "2") (pinfunction "2_2") (pintype "passive"))
      (node (ref "C23") (pin "2") (pinfunction "2_2") (pintype "passive"))
      (node (ref "C24") (pin "1") (pinfunction "1_1") (pintype "passive"))
      (node (ref "C25") (pin "1") (pinfunction "1_1") (pintype "passive"))
      (node (ref "C3") (pin "2") (pinfunction "C+_2") (pintype "passive"))
      (node (ref "C4") (pin "1") (pinfunction "1_1") (pintype "passive"))
      (node (ref "C5") (pin "1") (pinfunction "1_1") (pintype "passive"))
      (node (ref "C6") (pin "1") (pinfunction "1_1") (pintype "passive"))
      (node (ref "C7") (pin "1") (pinfunction "1_1") (pintype "passive"))
      (node (ref "C8") (pin "1") (pinfunction "1_1") (pintype "passive"))
      (node (ref "D9") (pin "1") (pinfunction "A_1") (pintype "passive"))
      (node (ref "J13") (pin "4") (pinfunction "GND_4") (pintype "passive"))
      (node (ref "J16") (pin "11") (pinfunction "11_11") (pintype "passive"))
      (node (ref "J16") (pin "16") (pinfunction "16_16") (pintype "passive"))
      (node (ref "J16") (pin "20") (pinfunction "20_20") (pintype "passive"))
      (node (ref "J16") (pin "25") (pinfunction "25_25") (pintype "passive"))
      (node (ref "J16") (pin "7") (pinfunction "7_7") (pintype "passive"))
      (node (ref "J17") (pin "6") (pinfunction "GND_6") (pintype "passive"))
      (node (ref "J17") (pin "7") (pinfunction "GND_7") (pintype "passive"))
      (node (ref "J18") (pin "1") (pinfunction "1_1") (pintype "passive"))
      (node (ref "J18") (pin "2") (pinfunction "2_2") (pintype "passive"))
      (node (ref "J3") (pin "2") (pinfunction "2_2") (pintype "passive"))
      (node (ref "J8") (pin "2") (pinfunction "VBAT-_2") (pintype "passive"))
      (node (ref "J9") (pin "2") (pinfunction "VBAT-_2") (pintype "passive"))
      (node (ref "M15") (pin "2") (pinfunction "S_2") (pintype "passive"))
      (node (ref "M16") (pin "2") (pinfunction "S_2") (pintype "passive"))
      (node (ref "M18") (pin "2") (pinfunction "S_2") (pintype "passive"))
      (node (ref "M19") (pin "2") (pinfunction "S_2") (pintype "passive"))
      (node (ref "M2") (pin "2") (pinfunction "S_2") (pintype "passive"))
      (node (ref "M20") (pin "1") (pinfunction "G_1") (pintype "passive"))
      (node (ref "M21") (pin "2") (pinfunction "S_2") (pintype "passive"))
      (node (ref "M22") (pin "2") (pinfunction "S_2") (pintype "passive"))
      (node (ref "M23") (pin "2") (pinfunction "S_2") (pintype "passive"))
      (node (ref "M24") (pin "2") (pinfunction "S_2") (pintype "passive"))
      (node (ref "M3") (pin "2") (pinfunction "S_2") (pintype "passive"))
      (node (ref "M4") (pin "2") (pinfunction "S_2") (pintype "passive"))
      (node (ref "M6") (pin "2") (pinfunction "S_2") (pintype "passive"))
      (node (ref "M8") (pin "2") (pinfunction "S_2") (pintype "passive"))
      (node (ref "M9") (pin "2") (pinfunction "S_2") (pintype "passive"))
      (node (ref "R15") (pin "1") (pinfunction "1_1") (pintype "passive"))
      (node (ref "R16") (pin "1") (pinfunction "1_1") (pintype "passive"))
      (node (ref "R18") (pin "1") (pinfunction "1_1") (pintype "passive"))
      (node (ref "R23") (pin "1") (pinfunction "1_1") (pintype "passive"))
      (node (ref "R26") (pin "1") (pinfunction "1_1") (pintype "passive"))
      (node (ref "R32") (pin "1") (pinfunction "1_1") (pintype "passive"))
      (node (ref "R36") (pin "1") (pinfunction "1_1") (pintype "passive"))
      (node (ref "R38") (pin "1") (pinfunction "1_1") (pintype "passive"))
      (node (ref "R39") (pin "1") (pinfunction "1_1") (pintype "passive"))
      (node (ref "R4") (pin "1") (pinfunction "1_1") (pintype "passive"))
      (node (ref "R46") (pin "1") (pinfunction "1_1") (pintype "passive"))
      (node (ref "R47") (pin "1") (pinfunction "1_1") (pintype "passive"))
      (node (ref "R48") (pin "1") (pinfunction "1_1") (pintype "passive"))
      (node (ref "R52") (pin "1") (pinfunction "1_1") (pintype "passive"))
      (node (ref "R53") (pin "1") (pinfunction "1_1") (pintype "passive"))
      (node (ref "R55") (pin "1") (pinfunction "1_1") (pintype "passive"))
      (node (ref "R57") (pin "1") (pinfunction "1_1") (pintype "passive"))
      (node (ref "R58") (pin "1") (pinfunction "1_1") (pintype "passive"))
      (node (ref "R6") (pin "1") (pinfunction "1_1") (pintype "passive"))
      (node (ref "R60") (pin "1") (pinfunction "1_1") (pintype "passive"))
      (node (ref "R62") (pin "1") (pinfunction "1_1") (pintype "passive"))
      (node (ref "R63") (pin "1") (pinfunction "1_1") (pintype "passive"))
      (node (ref "R64") (pin "1") (pinfunction "1_1") (pintype "passive"))
      (node (ref "R65") (pin "1") (pinfunction "1_1") (pintype "passive"))
      (node (ref "R66") (pin "1") (pinfunction "1_1") (pintype "passive"))
      (node (ref "R67") (pin "1") (pinfunction "1_1") (pintype "passive"))
      (node (ref "R7") (pin "1") (pinfunction "1_1") (pintype "passive"))
      (node (ref "R9") (pin "1") (pinfunction "1_1") (pintype "passive"))
      (node (ref "TP11") (pin "1") (pinfunction "Test_Point_1") (pintype "passive"))
      (node (ref "TP8") (pin "1") (pinfunction "Test_Point_1") (pintype "passive"))
      (node (ref "U1") (pin "2") (pinfunction "GND_2") (pintype "passive"))
      (node (ref "U1") (pin "4") (pinfunction "GND_4") (pintype "passive"))
      (node (ref "U10") (pin "4") (pinfunction "VSS_4") (pintype "passive"))
      (node (ref "U10") (pin "7") (pinfunction "~{WC}_7") (pintype "passive"))
      (node (ref "U2") (pin "4") (pinfunction "GND_4") (pintype "passive"))
      (node (ref "U3") (pin "4") (pinfunction "GND_4") (pintype "passive"))
      (node (ref "U4") (pin "4") (pinfunction "GND_4") (pintype "passive"))
      (node (ref "U6") (pin "2") (pinfunction "GND_2") (pintype "passive"))
      (node (ref "U6") (pin "3") (pinfunction "REF2_3") (pintype "passive"))
      (node (ref "U8") (pin "4") (pinfunction "V-_4") (pintype "passive"))
      (node (ref "U9") (pin "4") (pinfunction "V-_4") (pintype "passive"))
    )
    (net (code "32") (name "Net-(D1-A)") (class "Default")
      (node (ref "C2") (pin "2") (pinfunction "2_2") (pintype "passive"))
      (node (ref "D1") (pin "1") (pinfunction "A_1") (pintype "passive"))
      (node (ref "D7") (pin "2") (pinfunction "K_2") (pintype "passive"))
      (node (ref "M1") (pin "2") (pinfunction "D_2") (pintype "passive"))
      (node (ref "M11") (pin "1") (pinfunction "G_1") (pintype "passive"))
      (node (ref "R41") (pin "2") (pinfunction "2_2") (pintype "passive"))
      (node (ref "TP17") (pin "1") (pinfunction "Test_Point_1") (pintype "passive"))
      (node (ref "TP93") (pin "1") (pinfunction "Test_Point_1") (pintype "passive"))
    )
    (net (code "33") (name "Net-(D2-A)") (class "Default")
      (node (ref "D2") (pin "2") (pinfunction "A_2") (pintype "passive"))
      (node (ref "D4") (pin "2") (pinfunction "A_2") (pintype "passive"))
      (node (ref "M1") (pin "1") (pinfunction "G_1") (pintype "passive"))
      (node (ref "R10") (pin "2") (pinfunction "2_2") (pintype "passive"))
      (node (ref "TP100") (pin "1") (pinfunction "Test_Point_1") (pintype "passive"))
    )
    (net (code "34") (name "Net-(D2-K)") (class "Default")
      (node (ref "D2") (pin "1") (pinfunction "K_1") (pintype "passive"))
      (node (ref "M2") (pin "3") (pinfunction "D_3") (pintype "passive"))
      (node (ref "TP96") (pin "1") (pinfunction "Test_Point_1") (pintype "passive"))
    )
    (net (code "35") (name "Net-(D3-K)") (class "Default")
      (node (ref "D3") (pin "2") (pinfunction "K_2") (pintype "passive"))
      (node (ref "J1") (pin "2") (pinfunction "2_2") (pintype "passive"))
      (node (ref "M3") (pin "1") (pinfunction "G_1") (pintype "passive"))
      (node (ref "R6") (pin "2") (pinfunction "2_2") (pintype "passive"))
      (node (ref "TP83") (pin "1") (pinfunction "Test_Point_1") (pintype "passive"))
    )
    (net (code "36") (name "Net-(D4-K)") (class "Default")
      (node (ref "D4") (pin "1") (pinfunction "K_1") (pintype "passive"))
      (node (ref "M4") (pin "3") (pinfunction "D_3") (pintype "passive"))
      (node (ref "TP101") (pin "1") (pinfunction "Test_Point_1") (pintype "passive"))
    )
    (net (code "37") (name "Net-(D5-A)") (class "Default")
      (node (ref "D5") (pin "2") (pinfunction "A_2") (pintype "passive"))
      (node (ref "R8") (pin "1") (pinfunction "1_1") (pintype "passive"))
    )
    (net (code "38") (name "Net-(D5-K)") (class "Default")
      (node (ref "D5") (pin "1") (pinfunction "K_1") (pintype "passive"))
      (node (ref "M6") (pin "3") (pinfunction "D_3") (pintype "passive"))
      (node (ref "TP63") (pin "1") (pinfunction "Test_Point_1") (pintype "passive"))
    )
    (net (code "39") (name "Net-(D6-K)") (class "Default")
      (node (ref "D6") (pin "2") (pinfunction "K_2") (pintype "passive"))
      (node (ref "J7") (pin "2") (pinfunction "2_2") (pintype "passive"))
      (node (ref "M8") (pin "1") (pinfunction "G_1") (pintype "passive"))
      (node (ref "R23") (pin "2") (pinfunction "2_2") (pintype "passive"))
    )
    (net (code "40") (name "Net-(D7-A)") (class "Default")
      (node (ref "D7") (pin "1") (pinfunction "A_1") (pintype "passive"))
      (node (ref "M13") (pin "2") (pinfunction "D_2") (pintype "passive"))
      (node (ref "TP20") (pin "1") (pinfunction "Test_Point_1") (pintype "passive"))
    )
    (net (code "41") (name "Net-(D8-A)") (class "Default")
      (node (ref "D8") (pin "2") (pinfunction "A_2") (pintype "passive"))
      (node (ref "R34") (pin "1") (pinfunction "1_1") (pintype "passive"))
      (node (ref "TP12") (pin "1") (pinfunction "Test_Point_1") (pintype "passive"))
    )
    (net (code "42") (name "Net-(D8-K)") (class "Default")
      (node (ref "D8") (pin "1") (pinfunction "K_1") (pintype "passive"))
      (node (ref "M20") (pin "3") (pinfunction "D_3") (pintype "passive"))
      (node (ref "TP13") (pin "1") (pinfunction "Test_Point_1") (pintype "passive"))
    )
    (net (code "43") (name "Net-(D9-K)") (class "Default")
      (node (ref "D9") (pin "2") (pinfunction "K_2") (pintype "passive"))
      (node (ref "M13") (pin "1") (pinfunction "G_1") (pintype "passive"))
      (node (ref "R33") (pin "1") (pinfunction "1_1") (pintype "passive"))
      (node (ref "TP18") (pin "1") (pinfunction "Test_Point_1") (pintype "passive"))
    )
    (net (code "44") (name "Net-(D10-K)") (class "Default")
      (node (ref "D10") (pin "2") (pinfunction "K_2") (pintype "passive"))
      (node (ref "J10") (pin "2") (pinfunction "2_2") (pintype "passive"))
      (node (ref "R39") (pin "2") (pinfunction "2_2") (pintype "passive"))
      (node (ref "TP29") (pin "1") (pinfunction "Test_Point_1") (pintype "passive"))
      (node (ref "TP31") (pin "1") (pinfunction "Test_Point_1") (pintype "passive"))
      (node (ref "U7") (pin "7") (pinfunction "IN2-_7") (pintype "passive"))
    )
    (net (code "45") (name "Net-(D11-K)") (class "Default")
      (node (ref "D11") (pin "2") (pinfunction "K_2") (pintype "passive"))
      (node (ref "J22") (pin "1") (pinfunction "1_1") (pintype "passive"))
      (node (ref "M2") (pin "1") (pinfunction "G_1") (pintype "passive"))
      (node (ref "R4") (pin "2") (pinfunction "2_2") (pintype "passive"))
      (node (ref "TP99") (pin "1") (pinfunction "Test_Point_1") (pintype "passive"))
    )
    (net (code "46") (name "Net-(J12-(ADC2)PC2)") (class "Default")
      (node (ref "J12") (pin "3") (pinfunction "(ADC2)PC2_3") (pintype "passive"))
      (node (ref "M26") (pin "2") (pinfunction "S_2") (pintype "passive"))
      (node (ref "R66") (pin "2") (pinfunction "2_2") (pintype "passive"))
      (node (ref "R67") (pin "2") (pinfunction "2_2") (pintype "passive"))
      (node (ref "TP59") (pin "1") (pinfunction "Test_Point_1") (pintype "passive"))
      (node (ref "TP60") (pin "1") (pinfunction "Test_Point_1") (pintype "passive"))
      (node (ref "U9") (pin "2") (pinfunction "IN1-_2") (pintype "passive"))
    )
    (net (code "47") (name "Net-(J12-(ADC3)PC3)") (class "Default")
      (node (ref "J12") (pin "4") (pinfunction "(ADC3)PC3_4") (pintype "passive"))
      (node (ref "M25") (pin "2") (pinfunction "S_2") (pintype "passive"))
      (node (ref "R64") (pin "2") (pinfunction "2_2") (pintype "passive"))
      (node (ref "R65") (pin "2") (pinfunction "2_2") (pintype "passive"))
      (node (ref "TP58") (pin "1") (pinfunction "Test_Point_1") (pintype "passive"))
      (node (ref "U9") (pin "7") (pinfunction "IN2-_7") (pintype "passive"))
    )
    (net (code "48") (name "Net-(M3-D)") (class "Default")
      (node (ref "M3") (pin "3") (pinfunction "D_3") (pintype "passive"))
      (node (ref "R2") (pin "1") (pinfunction "1_1") (pintype "passive"))
      (node (ref "TP81") (pin "1") (pinfunction "Test_Point_1") (pintype "passive"))
      (node (ref "U3") (pin "2") (pinfunction "EN_2") (pintype "passive"))
    )
    (net (code "49") (name "Net-(M5-G)") (class "Default")
      (node (ref "J5") (pin "2") (pinfunction "2_2") (pintype "passive"))
      (node (ref "M5") (pin "1") (pinfunction "G_1") (pintype "passive"))
      (node (ref "M7") (pin "2") (pinfunction "D_2") (pintype "passive"))
      (node (ref "R15") (pin "2") (pinfunction "2_2") (pintype "passive"))
      (node (ref "TP64") (pin "1") (pinfunction "Test_Point_1") (pintype "passive"))
    )
    (net (code "50") (name "Net-(M7-G)") (class "Default")
      (node (ref "M7") (pin "1") (pinfunction "G_1") (pintype "passive"))
      (node (ref "M9") (pin "3") (pinfunction "D_3") (pintype "passive"))
      (node (ref "R17") (pin "1") (pinfunction "1_1") (pintype "passive"))
      (node (ref "TP69") (pin "1") (pinfunction "Test_Point_1") (pintype "passive"))
    )
    (net (code "51") (name "Net-(M8-D)") (class "Default")
      (node (ref "M8") (pin "3") (pinfunction "D_3") (pintype "passive"))
      (node (ref "R11") (pin "1") (pinfunction "1_1") (pintype "passive"))
      (node (ref "U4") (pin "2") (pinfunction "EN_2") (pintype "passive"))
    )
    (net (code "52") (name "Net-(M10-G)") (class "Default")
      (node (ref "M10") (pin "1") (pinfunction "G_1") (pintype "passive"))
      (node (ref "R32") (pin "2") (pinfunction "2_2") (pintype "passive"))
      (node (ref "TP9") (pin "1") (pinfunction "Test_Point_1") (pintype "passive"))
    )
    (net (code "53") (name "Net-(M10-S)") (class "Default")
      (node (ref "M10") (pin "3") (pinfunction "S_3") (pintype "passive"))
      (node (ref "M11") (pin "3") (pinfunction "S_3") (pintype "passive"))
      (node (ref "M14") (pin "3") (pinfunction "D_3") (pintype "passive"))
      (node (ref "TP6") (pin "1") (pinfunction "Test_Point_1") (pintype "passive"))
    )
    (net (code "54") (name "Net-(M11-D)") (class "Default")
      (node (ref "M11") (pin "4") (pinfunction "D_4") (pintype "passive"))
      (node (ref "M6") (pin "1") (pinfunction "G_1") (pintype "passive"))
      (node (ref "R16") (pin "2") (pinfunction "2_2") (pintype "passive"))
      (node (ref "R28") (pin "2") (pinfunction "2_2") (pintype "passive"))
      (node (ref "R31") (pin "1") (pinfunction "1_1") (pintype "passive"))
      (node (ref "TP7") (pin "1") (pinfunction "Test_Point_1") (pintype "passive"))
      (node (ref "TP74") (pin "1") (pinfunction "Test_Point_1") (pintype "passive"))
    )
    (net (code "55") (name "Net-(M12-D)") (class "Default")
      (node (ref "M12") (pin "3") (pinfunction "D_3") (pintype "passive"))
      (node (ref "TP23") (pin "1") (pinfunction "Test_Point_1") (pintype "passive"))
      (node (ref "U7") (pin "1") (pinfunction "OUT1_1") (pintype "passive"))
    )
    (net (code "56") (name "Net-(M12-G)") (class "Default")
      (node (ref "M12") (pin "1") (pinfunction "G_1") (pintype "passive"))
      (node (ref "R30") (pin "2") (pinfunction "2_2") (pintype "passive"))
      (node (ref "TP24") (pin "1") (pinfunction "Test_Point_1") (pintype "passive"))
      (node (ref "U7") (pin "6") (pinfunction "OUT2_6") (pintype "passive"))
    )
    (net (code "57") (name "Net-(M12-S)") (class "Default")
      (node (ref "M12") (pin "2") (pinfunction "S_2") (pintype "passive"))
      (node (ref "M17") (pin "1") (pinfunction "G_1") (pintype "passive"))
      (node (ref "R27") (pin "2") (pinfunction "2_2") (pintype "passive"))
      (node (ref "TP21") (pin "1") (pinfunction "Test_Point_1") (pintype "passive"))
    )
    (net (code "58") (name "Net-(M13-S)") (class "Default")
      (node (ref "M13") (pin "3") (pinfunction "S_3") (pintype "passive"))
      (node (ref "M14") (pin "2") (pinfunction "S_2") (pintype "passive"))
      (node (ref "R33") (pin "2") (pinfunction "2_2") (pintype "passive"))
      (node (ref "TP15") (pin "1") (pinfunction "Test_Point_1") (pintype "passive"))
    )
    (net (code "59") (name "Net-(M14-G)") (class "Default")
      (node (ref "M14") (pin "1") (pinfunction "G_1") (pintype "passive"))
      (node (ref "M18") (pin "3") (pinfunction "D_3") (pintype "passive"))
      (node (ref "R35") (pin "1") (pinfunction "1_1") (pintype "passive"))
      (node (ref "TP16") (pin "1") (pinfunction "Test_Point_1") (pintype "passive"))
    )
    (net (code "60") (name "Net-(M15-D)") (class "Default")
      (node (ref "M15") (pin "3") (pinfunction "D_3") (pintype "passive"))
      (node (ref "TP75") (pin "1") (pinfunction "Test_Point_1") (pintype "passive"))
      (node (ref "U5") (pin "1") (pinfunction "BK_1") (pintype "passive"))
    )
    (net (code "61") (name "Net-(M16-D)") (class "Default")
      (node (ref "M16") (pin "3") (pinfunction "D_3") (pintype "passive"))
      (node (ref "TP76") (pin "1") (pinfunction "Test_Point_1") (pintype "passive"))
      (node (ref "U5") (pin "5") (pinfunction "GK_5") (pintype "passive"))
    )
    (net (code "62") (name "Net-(M17-S)") (class "Default")
      (node (ref "M17") (pin "3") (pinfunction "S_3") (pintype "passive"))
      (node (ref "R52") (pin "2") (pinfunction "2_2") (pintype "passive"))
      (node (ref "TP39") (pin "1") (pinfunction "Test_Point_1") (pintype "passive"))
      (node (ref "U7") (pin "2") (pinfunction "IN1-_2") (pintype "passive"))
    )
    (net (code "63") (name "Net-(M19-D)") (class "Default")
      (node (ref "M19") (pin "3") (pinfunction "D_3") (pintype "passive"))
      (node (ref "TP78") (pin "1") (pinfunction "Test_Point_1") (pintype "passive"))
      (node (ref "U5") (pin "3") (pinfunction "RK_3") (pintype "passive"))
    )
    (net (code "64") (name "Net-(M21-D)") (class "Default")
      (node (ref "M21") (pin "3") (pinfunction "D_3") (pintype "passive"))
      (node (ref "M23") (pin "1") (pinfunction "G_1") (pintype "passive"))
      (node (ref "M24") (pin "3") (pinfunction "D_3") (pintype "passive"))
      (node (ref "R50") (pin "1") (pinfunction "1_1") (pintype "passive"))
      (node (ref "TP47") (pin "1") (pinfunction "Test_Point_1") (pintype "passive"))
    )
    (net (code "65") (name "Net-(M21-G)") (class "Default")
      (node (ref "M21") (pin "1") (pinfunction "G_1") (pintype "passive"))
      (node (ref "R58") (pin "2") (pinfunction "2_2") (pintype "passive"))
      (node (ref "TP49") (pin "1") (pinfunction "Test_Point_1") (pintype "passive"))
      (node (ref "U8") (pin "6") (pinfunction "OUT2_6") (pintype "passive"))
    )
    (net (code "66") (name "Net-(M22-G)") (class "Default")
      (node (ref "J11") (pin "1") (pinfunction "1_1") (pintype "passive"))
      (node (ref "M22") (pin "1") (pinfunction "G_1") (pintype "passive"))
      (node (ref "R57") (pin "2") (pinfunction "2_2") (pintype "passive"))
      (node (ref "TP50") (pin "1") (pinfunction "Test_Point_1") (pintype "passive"))
    )
    (net (code "67") (name "Net-(M25-D)") (class "Default")
      (node (ref "M25") (pin "3") (pinfunction "D_3") (pintype "passive"))
      (node (ref "R56") (pin "1") (pinfunction "1_1") (pintype "passive"))
    )
    (net (code "68") (name "Net-(M25-G)") (class "Default")
      (node (ref "M25") (pin "1") (pinfunction "G_1") (pintype "passive"))
      (node (ref "R60") (pin "2") (pinfunction "2_2") (pintype "passive"))
      (node (ref "TP55") (pin "1") (pinfunction "Test_Point_1") (pintype "passive"))
      (node (ref "U9") (pin "6") (pinfunction "OUT2_6") (pintype "passive"))
    )
    (net (code "69") (name "Net-(M26-D)") (class "Default")
      (node (ref "M26") (pin "3") (pinfunction "D_3") (pintype "passive"))
      (node (ref "R59") (pin "1") (pinfunction "1_1") (pintype "passive"))
      (node (ref "TP53") (pin "1") (pinfunction "Test_Point_1") (pintype "passive"))
    )
    (net (code "70") (name "Net-(M26-G)") (class "Default")
      (node (ref "M26") (pin "1") (pinfunction "G_1") (pintype "passive"))
      (node (ref "R62") (pin "2") (pinfunction "2_2") (pintype "passive"))
      (node (ref "TP54") (pin "1") (pinfunction "Test_Point_1") (pintype "passive"))
      (node (ref "U9") (pin "1") (pinfunction "OUT1_1") (pintype "passive"))
    )
    (net (code "71") (name "Net-(TP25-Test_Point)") (class "Default")
      (node (ref "R29") (pin "1") (pinfunction "1_1") (pintype "passive"))
      (node (ref "R37") (pin "2") (pinfunction "2_2") (pintype "passive"))
      (node (ref "TP25") (pin "1") (pinfunction "Test_Point_1") (pintype "passive"))
    )
    (net (code "72") (name "Net-(TP26-Test_Point)") (class "Default")
      (node (ref "R37") (pin "1") (pinfunction "1_1") (pintype "passive"))
      (node (ref "R48") (pin "2") (pinfunction "2_2") (pintype "passive"))
      (node (ref "TP26") (pin "1") (pinfunction "Test_Point_1") (pintype "passive"))
      (node (ref "U7") (pin "3") (pinfunction "IN1+_3") (pintype "passive"))
    )
    (net (code "73") (name "Net-(TP33-Test_Point)") (class "Default")
      (node (ref "R54") (pin "1") (pinfunction "1_1") (pintype "passive"))
      (node (ref "R55") (pin "2") (pinfunction "2_2") (pintype "passive"))
      (node (ref "TP33") (pin "1") (pinfunction "Test_Point_1") (pintype "passive"))
      (node (ref "U7") (pin "8") (pinfunction "IN2+_8") (pintype "passive"))
    )
    (net (code "74") (name "Net-(TP34-Test_Point)") (class "Default")
      (node (ref "C16") (pin "1") (pinfunction "1_1") (pintype "passive"))
      (node (ref "C17") (pin "2") (pinfunction "2_2") (pintype "passive"))
      (node (ref "R31") (pin "2") (pinfunction "2_2") (pintype "passive"))
      (node (ref "TP34") (pin "1") (pinfunction "Test_Point_1") (pintype "passive"))
      (node (ref "U6") (pin "8") (pinfunction "IN+_8") (pintype "passive"))
    )
    (net (code "75") (name "Net-(TP37-Test_Point)") (class "Default")
      (node (ref "C17") (pin "1") (pinfunction "1_1") (pintype "passive"))
      (node (ref "C18") (pin "2") (pinfunction "2_2") (pintype "passive"))
      (node (ref "TP37") (pin "1") (pinfunction "Test_Point_1") (pintype "passive"))
    )
    (net (code "76") (name "Net-(TP38-Test_Point)") (class "Default")
      (node (ref "C18") (pin "1") (pinfunction "1_1") (pintype "passive"))
      (node (ref "C19") (pin "2") (pinfunction "2_2") (pintype "passive"))
      (node (ref "R40") (pin "2") (pinfunction "2_2") (pintype "passive"))
      (node (ref "TP38") (pin "1") (pinfunction "Test_Point_1") (pintype "passive"))
      (node (ref "U6") (pin "1") (pinfunction "IN-_1") (pintype "passive"))
    )
    (net (code "77") (name "Net-(TP40-Test_Point)") (class "Default")
      (node (ref "R42") (pin "1") (pinfunction "1_1") (pintype "passive"))
      (node (ref "R44") (pin "2") (pinfunction "2_2") (pintype "passive"))
      (node (ref "R45") (pin "2") (pinfunction "2_2") (pintype "passive"))
      (node (ref "TP40") (pin "1") (pinfunction "Test_Point_1") (pintype "passive"))
    )
    (net (code "78") (name "Net-(TP41-Test_Point)") (class "Default")
      (node (ref "R42") (pin "2") (pinfunction "2_2") (pintype "passive"))
      (node (ref "R43") (pin "2") (pinfunction "2_2") (pintype "passive"))
      (node (ref "TP41") (pin "1") (pinfunction "Test_Point_1") (pintype "passive"))
    )
    (net (code "79") (name "Net-(TP43-Test_Point)") (class "Default")
      (node (ref "R49") (pin "1") (pinfunction "1_1") (pintype "passive"))
      (node (ref "TP43") (pin "1") (pinfunction "Test_Point_1") (pintype "passive"))
      (node (ref "U8") (pin "1") (pinfunction "OUT1_1") (pintype "passive"))
      (node (ref "U8") (pin "2") (pinfunction "IN1-_2") (pintype "passive"))
      (node (ref "U8") (pin "7") (pinfunction "IN2-_7") (pintype "passive"))
    )
    (net (code "80") (name "Net-(TP44-Test_Point)") (class "Default")
      (node (ref "R44") (pin "1") (pinfunction "1_1") (pintype "passive"))
      (node (ref "R45") (pin "1") (pinfunction "1_1") (pintype "passive"))
      (node (ref "R53") (pin "2") (pinfunction "2_2") (pintype "passive"))
      (node (ref "TP44") (pin "1") (pinfunction "Test_Point_1") (pintype "passive"))
      (node (ref "U8") (pin "3") (pinfunction "IN1+_3") (pintype "passive"))
    )
    (net (code "81") (name "Net-(TP45-Test_Point)") (class "Default")
      (node (ref "TP45") (pin "1") (pinfunction "Test_Point_1") (pintype "passive"))
      (node (ref "U6") (pin "5") (pinfunction "OUT_5") (pintype "passive"))
      (node (ref "U8") (pin "8") (pinfunction "IN2+_8") (pintype "passive"))
      (node (ref "U9") (pin "8") (pinfunction "IN2+_8") (pintype "passive"))
    )
    (net (code "82") (name "Net-(TP57-Test_Point)") (class "Default")
      (node (ref "R61") (pin "1") (pinfunction "1_1") (pintype "passive"))
      (node (ref "R63") (pin "2") (pinfunction "2_2") (pintype "passive"))
      (node (ref "TP57") (pin "1") (pinfunction "Test_Point_1") (pintype "passive"))
      (node (ref "U9") (pin "3") (pinfunction "IN1+_3") (pintype "passive"))
    )
    (net (code "83") (name "Net-(TP67-Test_Point)") (class "Default")
      (node (ref "R19") (pin "1") (pinfunction "1_1") (pintype "passive"))
      (node (ref "R24") (pin "2") (pinfunction "2_2") (pintype "passive"))
      (node (ref "TP67") (pin "1") (pinfunction "Test_Point_1") (pintype "passive"))
    )
    (net (code "84") (name "Net-(TP68-Test_Point)") (class "Default")
      (node (ref "R22") (pin "1") (pinfunction "1_1") (pintype "passive"))
      (node (ref "R25") (pin "2") (pinfunction "2_2") (pintype "passive"))
      (node (ref "TP68") (pin "1") (pinfunction "Test_Point_1") (pintype "passive"))
    )
    (net (code "85") (name "Net-(TP70-Test_Point)") (class "Default")
      (node (ref "R20") (pin "1") (pinfunction "1_1") (pintype "passive"))
      (node (ref "R21") (pin "1") (pinfunction "1_1") (pintype "passive"))
      (node (ref "TP70") (pin "1") (pinfunction "Test_Point_1") (pintype "passive"))
      (node (ref "U5") (pin "4") (pinfunction "RA_4") (pintype "passive"))
    )
    (net (code "86") (name "Net-(TP72-Test_Point)") (class "Default")
      (node (ref "R24") (pin "1") (pinfunction "1_1") (pintype "passive"))
      (node (ref "TP72") (pin "1") (pinfunction "Test_Point_1") (pintype "passive"))
      (node (ref "U5") (pin "2") (pinfunction "BA_2") (pintype "passive"))
    )
    (net (code "87") (name "Net-(TP73-Test_Point)") (class "Default")
      (node (ref "R25") (pin "1") (pinfunction "1_1") (pintype "passive"))
      (node (ref "TP73") (pin "1") (pinfunction "Test_Point_1") (pintype "passive"))
      (node (ref "U5") (pin "6") (pinfunction "GA_6") (pintype "passive"))
    )
    (net (code "88") (name "Net-(TP82-Test_Point)") (class "Default")
      (node (ref "R3") (pin "1") (pinfunction "1_1") (pintype "passive"))
      (node (ref "R5") (pin "2") (pinfunction "2_2") (pintype "passive"))
      (node (ref "TP82") (pin "1") (pinfunction "Test_Point_1") (pintype "passive"))
    )
    (net (code "89") (name "Net-(TP84-Test_Point)") (class "Default")
      (node (ref "R5") (pin "1") (pinfunction "1_1") (pintype "passive"))
      (node (ref "R7") (pin "2") (pinfunction "2_2") (pintype "passive"))
      (node (ref "TP84") (pin "1") (pinfunction "Test_Point_1") (pintype "passive"))
      (node (ref "TP85") (pin "1") (pinfunction "Test_Point_1") (pintype "passive"))
      (node (ref "U3") (pin "1") (pinfunction "FB_1") (pintype "passive"))
    )
    (net (code "90") (name "Net-(TP87-Test_Point)") (class "Default")
      (node (ref "L1") (pin "2") (pinfunction "2_2") (pintype "passive"))
      (node (ref "TP87") (pin "1") (pinfunction "Test_Point_1") (pintype "passive"))
      (node (ref "U3") (pin "5") (pinfunction "SW_5") (pintype "passive"))
    )
    (net (code "91") (name "Net-(TP88-Test_Point)") (class "Default")
      (node (ref "R12") (pin "1") (pinfunction "1_1") (pintype "passive"))
      (node (ref "R18") (pin "2") (pinfunction "2_2") (pintype "passive"))
      (node (ref "TP88") (pin "1") (pinfunction "Test_Point_1") (pintype "passive"))
      (node (ref "U4") (pin "1") (pinfunction "FB_1") (pintype "passive"))
    )
    (net (code "92") (name "Net-(TP89-Test_Point)") (class "Default")
      (node (ref "R12") (pin "2") (pinfunction "2_2") (pintype "passive"))
      (node (ref "R13") (pin "1") (pinfunction "1_1") (pintype "passive"))
      (node (ref "TP89") (pin "1") (pinfunction "Test_Point_1") (pintype "passive"))
    )
    (net (code "93") (name "Net-(TP90-Test_Point)") (class "Default")
      (node (ref "R13") (pin "2") (pinfunction "2_2") (pintype "passive"))
      (node (ref "R14") (pin "1") (pinfunction "1_1") (pintype "passive"))
      (node (ref "TP90") (pin "1") (pinfunction "Test_Point_1") (pintype "passive"))
    )
    (net (code "94") (name "Net-(TP91-Test_Point)") (class "Default")
      (node (ref "L2") (pin "2") (pinfunction "2_2") (pintype "passive"))
      (node (ref "TP91") (pin "1") (pinfunction "Test_Point_1") (pintype "passive"))
      (node (ref "U4") (pin "5") (pinfunction "SW_5") (pintype "passive"))
    )
    (net (code "95") (name "Net-(TP95-Test_Point)") (class "Default")
      (node (ref "C2") (pin "1") (pinfunction "1_1") (pintype "passive"))
      (node (ref "R1") (pin "2") (pinfunction "2_2") (pintype "passive"))
      (node (ref "TP95") (pin "1") (pinfunction "Test_Point_1") (pintype "passive"))
    )
    (net (code "96") (name "Net-(U2-CFLY+)") (class "Default")
      (node (ref "C9") (pin "2") (pinfunction "2_2") (pintype "passive"))
      (node (ref "U2") (pin "5") (pinfunction "CFLY+_5") (pintype "passive"))
    )
    (net (code "97") (name "Net-(U2-CFLY-)") (class "Default")
      (node (ref "C9") (pin "1") (pinfunction "1_1") (pintype "passive"))
      (node (ref "U2") (pin "3") (pinfunction "CFLY-_3") (pintype "passive"))
    )
    (net (code "98") (name "unconnected-(J2-Pad1)") (class "Default")
      (node (ref "J2") (pin "1") (pinfunction "1_1") (pintype "passive"))
    )
    (net (code "99") (name "unconnected-(J3-Pad1)") (class "Default")
      (node (ref "J3") (pin "1") (pinfunction "1_1") (pintype "passive"))
    )
    (net (code "100") (name "unconnected-(J4-Pad1)") (class "Default")
      (node (ref "J4") (pin "1") (pinfunction "1_1") (pintype "passive"))
    )
    (net (code "101") (name "unconnected-(J6-Pad1)") (class "Default")
      (node (ref "J6") (pin "1") (pinfunction "1_1") (pintype "passive"))
    )
    (net (code "102") (name "unconnected-(J11-Pad2)") (class "Default")
      (node (ref "J11") (pin "2") (pinfunction "2_2") (pintype "passive+no_connect"))
    )
    (net (code "103") (name "unconnected-(J11-Pad3)") (class "Default")
      (node (ref "J11") (pin "3") (pinfunction "3_3") (pintype "passive+no_connect"))
    )
    (net (code "104") (name "unconnected-(J12-(ADC0)PC0-Pad1)") (class "Default")
      (node (ref "J12") (pin "1") (pinfunction "(ADC0)PC0_1") (pintype "passive"))
    )
    (net (code "105") (name "unconnected-(J12-(ADC1)PC1-Pad2)") (class "Default")
      (node (ref "J12") (pin "2") (pinfunction "(ADC1)PC1_2") (pintype "passive"))
    )
    (net (code "106") (name "unconnected-(J12-(ADC4)PC4-Pad5)") (class "Default")
      (node (ref "J12") (pin "5") (pinfunction "(ADC4)PC4_5") (pintype "passive"))
    )
    (net (code "107") (name "unconnected-(J13-AREF-Pad3)") (class "Default")
      (node (ref "J13") (pin "3") (pinfunction "AREF_3") (pintype "passive+no_connect"))
    )
    (net (code "108") (name "unconnected-(J14-Pad1)") (class "Default")
      (node (ref "J14") (pin "1") (pinfunction "1_1") (pintype "passive+no_connect"))
    )
    (net (code "109") (name "unconnected-(J14-Pad2)") (class "Default")
      (node (ref "J14") (pin "2") (pinfunction "2_2") (pintype "passive+no_connect"))
    )
    (net (code "110") (name "unconnected-(J14-Pad3)") (class "Default")
      (node (ref "J14") (pin "3") (pinfunction "3_3") (pintype "passive+no_connect"))
    )
    (net (code "111") (name "unconnected-(J14-Pad4)") (class "Default")
      (node (ref "J14") (pin "4") (pinfunction "4_4") (pintype "passive+no_connect"))
    )
    (net (code "112") (name "unconnected-(J14-Pad5)") (class "Default")
      (node (ref "J14") (pin "5") (pinfunction "5_5") (pintype "passive+no_connect"))
    )
    (net (code "113") (name "unconnected-(J14-Pad6)") (class "Default")
      (node (ref "J14") (pin "6") (pinfunction "6_6") (pintype "passive+no_connect"))
    )
    (net (code "114") (name "unconnected-(J14-Pad7)") (class "Default")
      (node (ref "J14") (pin "7") (pinfunction "7_7") (pintype "passive+no_connect"))
    )
    (net (code "115") (name "unconnected-(J14-Pad8)") (class "Default")
      (node (ref "J14") (pin "8") (pinfunction "8_8") (pintype "passive+no_connect"))
    )
    (net (code "116") (name "unconnected-(J14-Pad9)") (class "Default")
      (node (ref "J14") (pin "9") (pinfunction "9_9") (pintype "passive+no_connect"))
    )
    (net (code "117") (name "unconnected-(J14-Pad10)") (class "Default")
      (node (ref "J14") (pin "10") (pinfunction "10_10") (pintype "passive+no_connect"))
    )
    (net (code "118") (name "unconnected-(J14-Pad11)") (class "Default")
      (node (ref "J14") (pin "11") (pinfunction "11_11") (pintype "passive+no_connect"))
    )
    (net (code "119") (name "unconnected-(J14-Pad12)") (class "Default")
      (node (ref "J14") (pin "12") (pinfunction "12_12") (pintype "passive+no_connect"))
    )
    (net (code "120") (name "unconnected-(J14-Pad13)") (class "Default")
      (node (ref "J14") (pin "13") (pinfunction "13_13") (pintype "passive+no_connect"))
    )
    (net (code "121") (name "unconnected-(J14-Pad14)") (class "Default")
      (node (ref "J14") (pin "14") (pinfunction "14_14") (pintype "passive+no_connect"))
    )
    (net (code "122") (name "unconnected-(J14-Pad15)") (class "Default")
      (node (ref "J14") (pin "15") (pinfunction "15_15") (pintype "passive+no_connect"))
    )
    (net (code "123") (name "unconnected-(J14-Pad16)") (class "Default")
      (node (ref "J14") (pin "16") (pinfunction "16_16") (pintype "passive+no_connect"))
    )
    (net (code "124") (name "unconnected-(J14-Pad17)") (class "Default")
      (node (ref "J14") (pin "17") (pinfunction "17_17") (pintype "passive+no_connect"))
    )
    (net (code "125") (name "unconnected-(J14-Pad18)") (class "Default")
      (node (ref "J14") (pin "18") (pinfunction "18_18") (pintype "passive+no_connect"))
    )
    (net (code "126") (name "unconnected-(J14-Pad19)") (class "Default")
      (node (ref "J14") (pin "19") (pinfunction "19_19") (pintype "passive+no_connect"))
    )
    (net (code "127") (name "unconnected-(J14-Pad20)") (class "Default")
      (node (ref "J14") (pin "20") (pinfunction "20_20") (pintype "passive+no_connect"))
    )
    (net (code "128") (name "unconnected-(J16-Pad1)") (class "Default")
      (node (ref "J16") (pin "1") (pinfunction "1_1") (pintype "passive+no_connect"))
    )
    (net (code "129") (name "unconnected-(J16-Pad2)") (class "Default")
      (node (ref "J16") (pin "2") (pinfunction "2_2") (pintype "passive+no_connect"))
    )
    (net (code "130") (name "unconnected-(J16-Pad3)") (class "Default")
      (node (ref "J16") (pin "3") (pinfunction "3_3") (pintype "passive+no_connect"))
    )
    (net (code "131") (name "unconnected-(J16-Pad4)") (class "Default")
      (node (ref "J16") (pin "4") (pinfunction "4_4") (pintype "passive+no_connect"))
    )
    (net (code "132") (name "unconnected-(J16-Pad6)") (class "Default")
      (node (ref "J16") (pin "6") (pinfunction "6_6") (pintype "passive+no_connect"))
    )
    (net (code "133") (name "unconnected-(J16-Pad10)") (class "Default")
      (node (ref "J16") (pin "10") (pinfunction "10_10") (pintype "passive+no_connect"))
    )
    (net (code "134") (name "unconnected-(J16-Pad12)") (class "Default")
      (node (ref "J16") (pin "12") (pinfunction "12_12") (pintype "passive+no_connect"))
    )
    (net (code "135") (name "unconnected-(J16-Pad26)") (class "Default")
      (node (ref "J16") (pin "26") (pinfunction "26_26") (pintype "passive+no_connect"))
    )
    (net (code "136") (name "unconnected-(J17-3.3V-Pad4)") (class "Default")
      (node (ref "J17") (pin "4") (pinfunction "3.3V_4") (pintype "passive+no_connect"))
    )
    (net (code "137") (name "unconnected-(J17-5V-Pad5)") (class "Default")
      (node (ref "J17") (pin "5") (pinfunction "5V_5") (pintype "passive+no_connect"))
    )
    (net (code "138") (name "unconnected-(J17-IOREF-Pad2)") (class "Default")
      (node (ref "J17") (pin "2") (pinfunction "IOREF_2") (pintype "passive+no_connect"))
    )
    (net (code "139") (name "unconnected-(J17-NC-Pad1)") (class "Default")
      (node (ref "J17") (pin "1") (pinfunction "NC_1") (pintype "passive+no_connect"))
    )
    (net (code "140") (name "unconnected-(J17-RESET-Pad3)") (class "Default")
      (node (ref "J17") (pin "3") (pinfunction "RESET_3") (pintype "passive+no_connect"))
    )
    (net (code "141") (name "unconnected-(J17-VIN-Pad8)") (class "Default")
      (node (ref "J17") (pin "8") (pinfunction "VIN_8") (pintype "passive+no_connect"))
    )
    (net (code "142") (name "unconnected-(J19-Pad1)") (class "Default")
      (node (ref "J19") (pin "1") (pinfunction "1_1") (pintype "passive+no_connect"))
    )
    (net (code "143") (name "unconnected-(J20-Pad1)") (class "Default")
      (node (ref "J20") (pin "1") (pinfunction "1_1") (pintype "passive+no_connect"))
    )
    (net (code "144") (name "unconnected-(J21-Pad1)") (class "Default")
      (node (ref "J21") (pin "1") (pinfunction "1_1") (pintype "passive+no_connect"))
    )
    (net (code "145") (name "unconnected-(J21-Pad2)") (class "Default")
      (node (ref "J21") (pin "2") (pinfunction "2_2") (pintype "passive+no_connect"))
    )
    (net (code "146") (name "unconnected-(J23-1-PadS1)") (class "Default")
      (node (ref "J23") (pin "S1") (pinfunction "1_S1") (pintype "passive+no_connect"))
    )
    (net (code "147") (name "unconnected-(J23-1-PadS2)") (class "Default")
      (node (ref "J23") (pin "S2") (pinfunction "1_S2") (pintype "passive+no_connect"))
    )
    (net (code "148") (name "unconnected-(J24-Pad1)") (class "Default")
      (node (ref "J24") (pin "1") (pinfunction "1_1") (pintype "passive+no_connect"))
    )
    (net (code "149") (name "unconnected-(J25-Pad1)") (class "Default")
      (node (ref "J25") (pin "1") (pinfunction "1_1") (pintype "passive+no_connect"))
    )
    (net (code "150") (name "unconnected-(U6-NC-Pad4)") (class "Default")
      (node (ref "U6") (pin "4") (pinfunction "NC_4") (pintype "passive+no_connect"))
    )
  )
)
